# ProPrj_cheap-board_2026-05-07.net
KiCad netlist of a schematic drawn in EasyEDA Pro
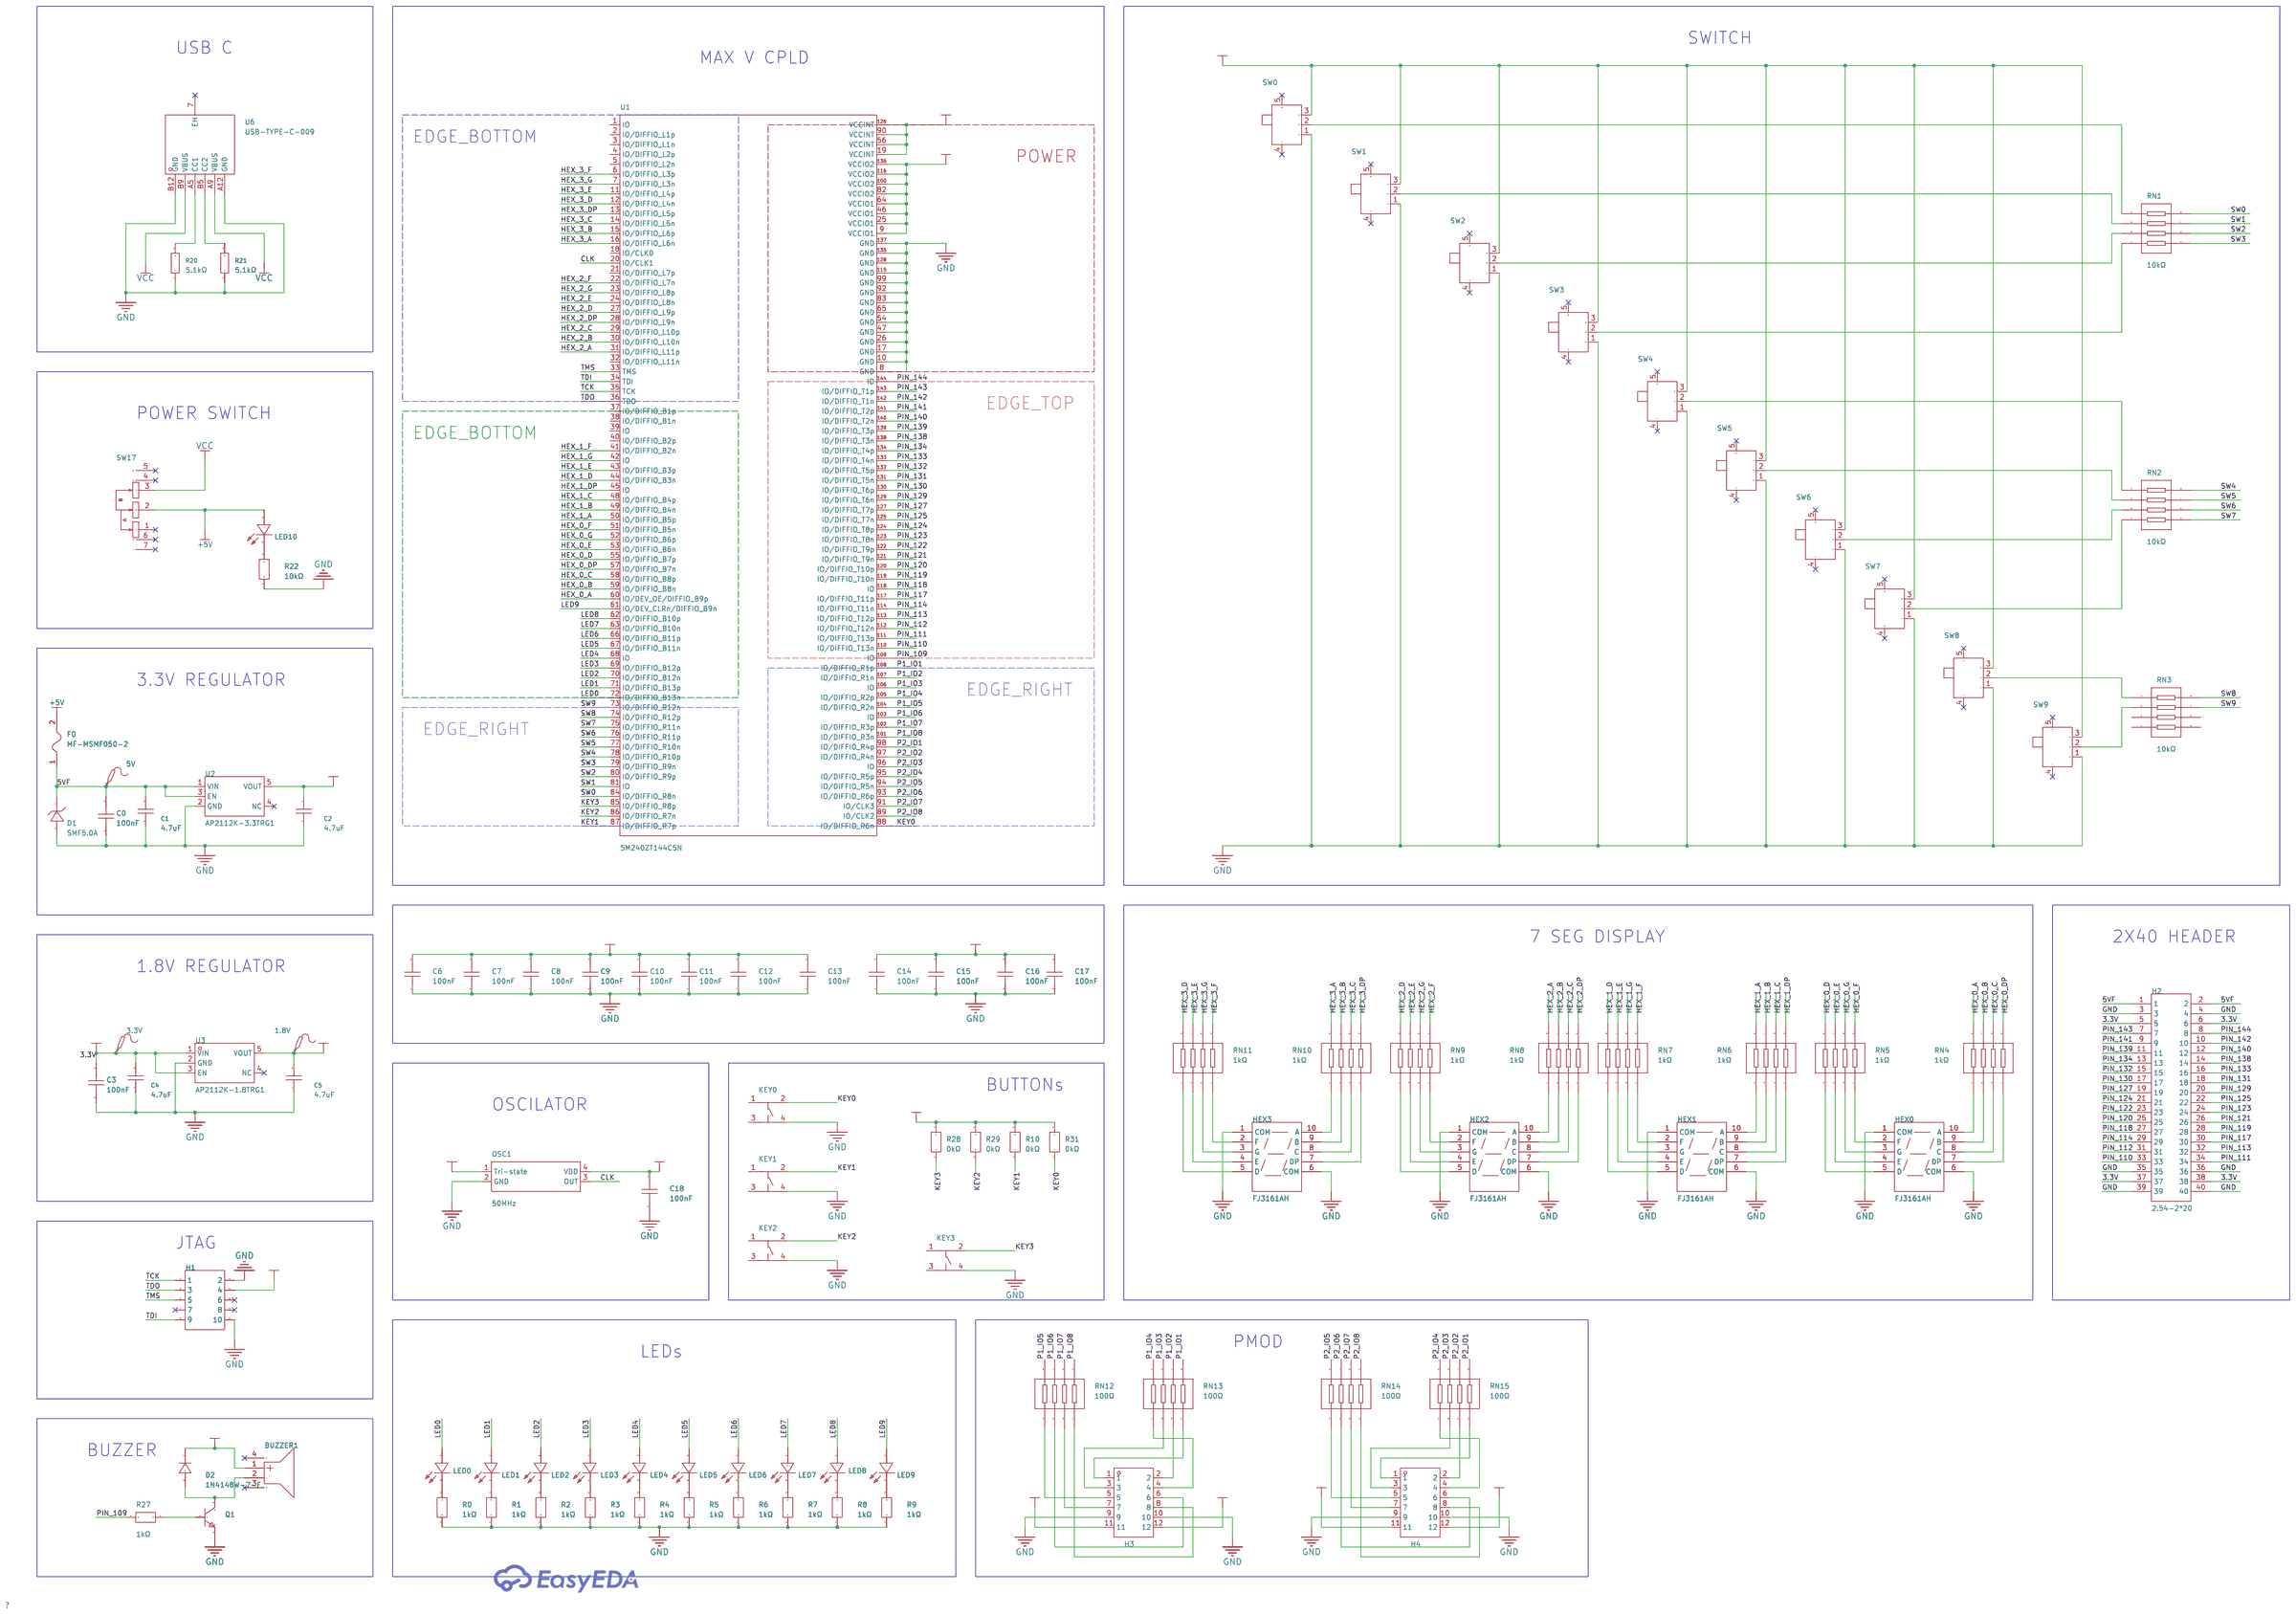
[diagram p0: schematic sheet]

(export (version "E")
  (design (tool "Eeschema 10.0.6"))
  (components
    (comp (ref "1.8V")
      (value "~")
      (footprint "easyedapro:Test-Point-0.5mm")
      (description "Test Point 测试点")
      (libsource (lib "easyedapro") (part "Test-Point"))
    )
    (comp (ref "3.3V")
      (value "~")
      (footprint "easyedapro:Test-Point-0.5mm")
      (description "Test Point 测试点")
      (libsource (lib "easyedapro") (part "Test-Point"))
    )
    (comp (ref "5V")
      (value "~")
      (footprint "easyedapro:Test-Point-0.5mm")
      (description "Test Point 测试点")
      (libsource (lib "easyedapro") (part "Test-Point"))
    )
    (comp (ref "BUZZER1")
      (value "2.7kHz")
      (footprint "easyedapro:BUZ-SMD_4P-L7.5-W7.5-P7.59-TL")
      (fields (field (name "Manufacturer Part") "MLT-7525") (field (name "Manufacturer") "华能"))
      (libsource (lib "easyedapro") (part "MLT-7525"))
    )
    (comp (ref "C0")
      (value "100nF")
      (footprint "easyedapro:C0603")
      (description "Capacitance:100nF Tolerance:±10% Tolerance:±10% Voltage Rating:50V Temperature Coefficient:X7R")
      (fields
        (field (name "Manufacturer Part") "CC0603KRX7R9BB104")
        (field (name "Manufacturer") "YAGEO(国巨)")
      )
      (libsource (lib "easyedapro") (part "CC0603KRX7R9BB104"))
    )
    (comp (ref "C1")
      (value "4.7uF")
      (footprint "easyedapro:C0603")
      (description "Capacitance:4.7uF Tolerance:±10% Tolerance:±10% Voltage Rating:16V Temperature Coefficient:X7R")
      (fields
        (field (name "Manufacturer Part") "CGA0603X7R475K160JT")
        (field (name "Manufacturer") "HRE(芯声)")
      )
      (libsource (lib "easyedapro") (part "CL10A475KP8NNNC"))
    )
    (comp (ref "C2")
      (value "4.7uF")
      (footprint "easyedapro:C0603")
      (description "Capacitance:4.7uF Tolerance:±10% Tolerance:±10% Voltage Rating:16V Temperature Coefficient:X7R")
      (fields
        (field (name "Manufacturer Part") "CGA0603X7R475K160JT")
        (field (name "Manufacturer") "HRE(芯声)")
      )
      (libsource (lib "easyedapro") (part "CL10A475KP8NNNC"))
    )
    (comp (ref "C3")
      (value "100nF")
      (footprint "easyedapro:C0603")
      (description "Capacitance:100nF Tolerance:±10% Tolerance:±10% Voltage Rating:50V Temperature Coefficient:X7R")
      (fields
        (field (name "Manufacturer Part") "CC0603KRX7R9BB104")
        (field (name "Manufacturer") "YAGEO(国巨)")
      )
      (libsource (lib "easyedapro") (part "CC0603KRX7R9BB104"))
    )
    (comp (ref "C4")
      (value "4.7uF")
      (footprint "easyedapro:C0603")
      (description "Capacitance:4.7uF Tolerance:±10% Tolerance:±10% Voltage Rating:16V Temperature Coefficient:X7R")
      (fields
        (field (name "Manufacturer Part") "CGA0603X7R475K160JT")
        (field (name "Manufacturer") "HRE(芯声)")
      )
      (libsource (lib "easyedapro") (part "CL10A475KP8NNNC"))
    )
    (comp (ref "C5")
      (value "4.7uF")
      (footprint "easyedapro:C0603")
      (description "Capacitance:4.7uF Tolerance:±10% Tolerance:±10% Voltage Rating:16V Temperature Coefficient:X7R")
      (fields
        (field (name "Manufacturer Part") "CGA0603X7R475K160JT")
        (field (name "Manufacturer") "HRE(芯声)")
      )
      (libsource (lib "easyedapro") (part "CL10A475KP8NNNC"))
    )
    (comp (ref "C6")
      (value "100nF")
      (footprint "easyedapro:C0603")
      (description "Capacitance:100nF Tolerance:±10% Tolerance:±10% Voltage Rating:50V Temperature Coefficient:X7R")
      (fields
        (field (name "Manufacturer Part") "CC0603KRX7R9BB104")
        (field (name "Manufacturer") "YAGEO(国巨)")
      )
      (libsource (lib "easyedapro") (part "CC0603KRX7R9BB104"))
    )
    (comp (ref "C7")
      (value "100nF")
      (footprint "easyedapro:C0603")
      (description "Capacitance:100nF Tolerance:±10% Tolerance:±10% Voltage Rating:50V Temperature Coefficient:X7R")
      (fields
        (field (name "Manufacturer Part") "CC0603KRX7R9BB104")
        (field (name "Manufacturer") "YAGEO(国巨)")
      )
      (libsource (lib "easyedapro") (part "CC0603KRX7R9BB104"))
    )
    (comp (ref "C8")
      (value "100nF")
      (footprint "easyedapro:C0603")
      (description "Capacitance:100nF Tolerance:±10% Tolerance:±10% Voltage Rating:50V Temperature Coefficient:X7R")
      (fields
        (field (name "Manufacturer Part") "CC0603KRX7R9BB104")
        (field (name "Manufacturer") "YAGEO(国巨)")
      )
      (libsource (lib "easyedapro") (part "CC0603KRX7R9BB104"))
    )
    (comp (ref "C9")
      (value "100nF")
      (footprint "easyedapro:C0603")
      (description "Capacitance:100nF Tolerance:±10% Tolerance:±10% Voltage Rating:50V Temperature Coefficient:X7R")
      (fields
        (field (name "Manufacturer Part") "CC0603KRX7R9BB104")
        (field (name "Manufacturer") "YAGEO(国巨)")
      )
      (libsource (lib "easyedapro") (part "CC0603KRX7R9BB104"))
    )
    (comp (ref "C10")
      (value "100nF")
      (footprint "easyedapro:C0603")
      (description "Capacitance:100nF Tolerance:±10% Tolerance:±10% Voltage Rating:50V Temperature Coefficient:X7R")
      (fields
        (field (name "Manufacturer Part") "CC0603KRX7R9BB104")
        (field (name "Manufacturer") "YAGEO(国巨)")
      )
      (libsource (lib "easyedapro") (part "CC0603KRX7R9BB104"))
    )
    (comp (ref "C11")
      (value "100nF")
      (footprint "easyedapro:C0603")
      (description "Capacitance:100nF Tolerance:±10% Tolerance:±10% Voltage Rating:50V Temperature Coefficient:X7R")
      (fields
        (field (name "Manufacturer Part") "CC0603KRX7R9BB104")
        (field (name "Manufacturer") "YAGEO(国巨)")
      )
      (libsource (lib "easyedapro") (part "CC0603KRX7R9BB104"))
    )
    (comp (ref "C12")
      (value "100nF")
      (footprint "easyedapro:C0603")
      (description "Capacitance:100nF Tolerance:±10% Tolerance:±10% Voltage Rating:50V Temperature Coefficient:X7R")
      (fields
        (field (name "Manufacturer Part") "CC0603KRX7R9BB104")
        (field (name "Manufacturer") "YAGEO(国巨)")
      )
      (libsource (lib "easyedapro") (part "CC0603KRX7R9BB104"))
    )
    (comp (ref "C13")
      (value "100nF")
      (footprint "easyedapro:C0603")
      (description "Capacitance:100nF Tolerance:±10% Tolerance:±10% Voltage Rating:50V Temperature Coefficient:X7R")
      (fields
        (field (name "Manufacturer Part") "CC0603KRX7R9BB104")
        (field (name "Manufacturer") "YAGEO(国巨)")
      )
      (libsource (lib "easyedapro") (part "CC0603KRX7R9BB104"))
    )
    (comp (ref "C14")
      (value "100nF")
      (footprint "easyedapro:C0603")
      (description "Capacitance:100nF Tolerance:±10% Tolerance:±10% Voltage Rating:50V Temperature Coefficient:X7R")
      (fields
        (field (name "Manufacturer Part") "CC0603KRX7R9BB104")
        (field (name "Manufacturer") "YAGEO(国巨)")
      )
      (libsource (lib "easyedapro") (part "CC0603KRX7R9BB104"))
    )
    (comp (ref "C15")
      (value "100nF")
      (footprint "easyedapro:C0603")
      (description "Capacitance:100nF Tolerance:±10% Tolerance:±10% Voltage Rating:50V Temperature Coefficient:X7R")
      (fields
        (field (name "Manufacturer Part") "CC0603KRX7R9BB104")
        (field (name "Manufacturer") "YAGEO(国巨)")
      )
      (libsource (lib "easyedapro") (part "CC0603KRX7R9BB104"))
    )
    (comp (ref "C16")
      (value "100nF")
      (footprint "easyedapro:C0603")
      (description "Capacitance:100nF Tolerance:±10% Tolerance:±10% Voltage Rating:50V Temperature Coefficient:X7R")
      (fields
        (field (name "Manufacturer Part") "CC0603KRX7R9BB104")
        (field (name "Manufacturer") "YAGEO(国巨)")
      )
      (libsource (lib "easyedapro") (part "CC0603KRX7R9BB104"))
    )
    (comp (ref "C17")
      (value "100nF")
      (footprint "easyedapro:C0603")
      (description "Capacitance:100nF Tolerance:±10% Tolerance:±10% Voltage Rating:50V Temperature Coefficient:X7R")
      (fields
        (field (name "Manufacturer Part") "CC0603KRX7R9BB104")
        (field (name "Manufacturer") "YAGEO(国巨)")
      )
      (libsource (lib "easyedapro") (part "CC0603KRX7R9BB104"))
    )
    (comp (ref "C18")
      (value "100nF")
      (footprint "easyedapro:C0603")
      (description "Capacitance:100nF Tolerance:±10% Tolerance:±10% Voltage Rating:50V Temperature Coefficient:X7R")
      (fields
        (field (name "Manufacturer Part") "CC0603KRX7R9BB104")
        (field (name "Manufacturer") "YAGEO(国巨)")
      )
      (libsource (lib "easyedapro") (part "CC0603KRX7R9BB104"))
    )
    (comp (ref "D1")
      (value "SMF5.0A")
      (footprint "easyedapro:SOD-123FL_L2.7-W1.8-LS3.8-RD")
      (fields (field (name "Manufacturer") "MDD(辰达半导体)"))
      (libsource (lib "easyedapro") (part "SMF5.0A_C193402"))
    )
    (comp (ref "D2")
      (value "1N4148W-7-F")
      (footprint "easyedapro:SOD-123_L2.7-W1.6-LS3.7-RD-1")
      (fields (field (name "Manufacturer") "DIODES(美台)"))
      (libsource (lib "easyedapro") (part "1N4148W-7-F"))
    )
    (comp (ref "F0")
      (value "MF-MSMF050-2")
      (footprint "easyedapro:F1812")
      (fields (field (name "Manufacturer") "BOURNS"))
      (libsource (lib "easyedapro") (part "MF-MSMF050-2"))
    )
    (comp (ref "H1")
      (value "2.54-2*5P简牛")
      (footprint "easyedapro:IDC-TH_10P-P2.54_C5665")
      (fields (field (name "Manufacturer") "BOOMELE(博穆精密)"))
      (libsource (lib "easyedapro") (part "HDR-IDC-2.54-2X5P"))
    )
    (comp (ref "H2")
      (value "2.54-2*20")
      (footprint "easyedapro:HDR-TH_40P-P2.54-V-F-R2-C20-S2.54")
      (fields (field (name "Manufacturer") "ZHOURI(洲日)"))
      (libsource (lib "easyedapro") (part "2.54-2*20"))
    )
    (comp (ref "H3")
      (value "HX PM2.54-2x6P WC")
      (footprint "easyedapro:HDR-TH_12P-P2.54-H-F-R2-C6-S2.54-W12.7-N")
      (fields (field (name "Manufacturer") "hanxia(韩下)"))
      (libsource (lib "easyedapro") (part "HX PM2.54-2X6P WC"))
    )
    (comp (ref "H4")
      (value "HX PM2.54-2x6P WC")
      (footprint "easyedapro:HDR-TH_12P-P2.54-H-F-R2-C6-S2.54-W12.7-N")
      (fields (field (name "Manufacturer") "hanxia(韩下)"))
      (libsource (lib "easyedapro") (part "HX PM2.54-2X6P WC"))
    )
    (comp (ref "HEX0")
      (value "FJ3161AH")
      (footprint "easyedapro:LED-SEG-TH_10P-L14.0-W7.5-P2.54-S5.08-TL")
      (description "Digit/Alpha Size(inch):0.36 Illumination Color:Red LED Polarity:Common Cathode")
      (fields (field (name "Manufacturer") "志浩"))
      (libsource (lib "easyedapro") (part "XL-DB3161SRBC"))
    )
    (comp (ref "HEX1")
      (value "FJ3161AH")
      (footprint "easyedapro:LED-SEG-TH_10P-L14.0-W7.5-P2.54-S5.08-TL")
      (description "Digit/Alpha Size(inch):0.36 Illumination Color:Red LED Polarity:Common Cathode")
      (fields (field (name "Manufacturer") "志浩"))
      (libsource (lib "easyedapro") (part "XL-DB3161SRBC"))
    )
    (comp (ref "HEX2")
      (value "FJ3161AH")
      (footprint "easyedapro:LED-SEG-TH_10P-L14.0-W7.5-P2.54-S5.08-TL")
      (description "Digit/Alpha Size(inch):0.36 Illumination Color:Red LED Polarity:Common Cathode")
      (fields (field (name "Manufacturer") "志浩"))
      (libsource (lib "easyedapro") (part "XL-DB3161SRBC"))
    )
    (comp (ref "HEX3")
      (value "FJ3161AH")
      (footprint "easyedapro:LED-SEG-TH_10P-L14.0-W7.5-P2.54-S5.08-TL")
      (description "Digit/Alpha Size(inch):0.36 Illumination Color:Red LED Polarity:Common Cathode")
      (fields (field (name "Manufacturer") "志浩"))
      (libsource (lib "easyedapro") (part "XL-DB3161SRBC"))
    )
    (comp (ref "KEY0")
      (value "KH-6X6X6H-STM")
      (footprint "easyedapro:SW-SMD_4P-L6.0-W6.0-P4.50-LS9.0_KH-6X6X6H-STM")
      (fields (field (name "Manufacturer") "kinghelm(金航标)"))
      (libsource (lib "easyedapro") (part "KH-6X6X6H-STM"))
    )
    (comp (ref "KEY1")
      (value "KH-6X6X6H-STM")
      (footprint "easyedapro:SW-SMD_4P-L6.0-W6.0-P4.50-LS9.0_KH-6X6X6H-STM")
      (fields (field (name "Manufacturer") "kinghelm(金航标)"))
      (libsource (lib "easyedapro") (part "KH-6X6X6H-STM"))
    )
    (comp (ref "KEY2")
      (value "KH-6X6X6H-STM")
      (footprint "easyedapro:SW-SMD_4P-L6.0-W6.0-P4.50-LS9.0_KH-6X6X6H-STM")
      (fields (field (name "Manufacturer") "kinghelm(金航标)"))
      (libsource (lib "easyedapro") (part "KH-6X6X6H-STM"))
    )
    (comp (ref "KEY3")
      (value "KH-6X6X6H-STM")
      (footprint "easyedapro:SW-SMD_4P-L6.0-W6.0-P4.50-LS9.0_KH-6X6X6H-STM")
      (fields (field (name "Manufacturer") "kinghelm(金航标)"))
      (libsource (lib "easyedapro") (part "KH-6X6X6H-STM"))
    )
    (comp (ref "LED0")
      (value "YLED0603R")
      (footprint "easyedapro:LED0805-R-RD")
      (fields (field (name "Manufacturer") "YONGYUTAI(永裕泰)"))
      (libsource (lib "easyedapro") (part "FC-2012HRK-620D"))
    )
    (comp (ref "LED1")
      (value "YLED0603R")
      (footprint "easyedapro:LED0805-R-RD")
      (fields (field (name "Manufacturer") "YONGYUTAI(永裕泰)"))
      (libsource (lib "easyedapro") (part "FC-2012HRK-620D"))
    )
    (comp (ref "LED2")
      (value "YLED0603R")
      (footprint "easyedapro:LED0805-R-RD")
      (fields (field (name "Manufacturer") "YONGYUTAI(永裕泰)"))
      (libsource (lib "easyedapro") (part "FC-2012HRK-620D"))
    )
    (comp (ref "LED3")
      (value "YLED0603R")
      (footprint "easyedapro:LED0805-R-RD")
      (fields (field (name "Manufacturer") "YONGYUTAI(永裕泰)"))
      (libsource (lib "easyedapro") (part "FC-2012HRK-620D"))
    )
    (comp (ref "LED4")
      (value "YLED0603R")
      (footprint "easyedapro:LED0805-R-RD")
      (fields (field (name "Manufacturer") "YONGYUTAI(永裕泰)"))
      (libsource (lib "easyedapro") (part "FC-2012HRK-620D"))
    )
    (comp (ref "LED5")
      (value "YLED0603R")
      (footprint "easyedapro:LED0805-R-RD")
      (fields (field (name "Manufacturer") "YONGYUTAI(永裕泰)"))
      (libsource (lib "easyedapro") (part "FC-2012HRK-620D"))
    )
    (comp (ref "LED6")
      (value "YLED0603R")
      (footprint "easyedapro:LED0805-R-RD")
      (fields (field (name "Manufacturer") "YONGYUTAI(永裕泰)"))
      (libsource (lib "easyedapro") (part "FC-2012HRK-620D"))
    )
    (comp (ref "LED7")
      (value "YLED0603R")
      (footprint "easyedapro:LED0805-R-RD")
      (fields (field (name "Manufacturer") "YONGYUTAI(永裕泰)"))
      (libsource (lib "easyedapro") (part "FC-2012HRK-620D"))
    )
    (comp (ref "LED8")
      (value "YLED0603R")
      (footprint "easyedapro:LED0805-R-RD")
      (fields (field (name "Manufacturer") "YONGYUTAI(永裕泰)"))
      (libsource (lib "easyedapro") (part "FC-2012HRK-620D"))
    )
    (comp (ref "LED9")
      (value "YLED0603R")
      (footprint "easyedapro:LED0805-R-RD")
      (fields (field (name "Manufacturer") "YONGYUTAI(永裕泰)"))
      (libsource (lib "easyedapro") (part "FC-2012HRK-620D"))
    )
    (comp (ref "LED10")
      (value "YLED0603R")
      (footprint "easyedapro:LED0805-R-RD")
      (fields (field (name "Manufacturer") "YONGYUTAI(永裕泰)"))
      (libsource (lib "easyedapro") (part "FC-2012HRK-620D"))
    )
    (comp (ref "OSC1")
      (value "50MHz")
      (footprint "easyedapro:OSC-SMD_4P-L3.2-W2.5-BL")
      (fields
        (field (name "Manufacturer Part") "OT2EL4C4JI-111OLP-50M")
        (field (name "Manufacturer") "YXC(扬兴晶振)")
      )
      (libsource (lib "easyedapro") (part "OT2EL4C4JI-111OLP-50M"))
    )
    (comp (ref "Q1")
      (value "MMBT3904LT1G")
      (footprint "easyedapro:SOT-23-3_L2.9-W1.6-P1.90-LS2.8-BR")
      (fields (field (name "Manufacturer") "onsemi(安森美)"))
      (libsource (lib "easyedapro") (part "MMBT3904LT1G"))
    )
    (comp (ref "R0")
      (value "1kΩ")
      (fields (field (name "Manufacturer Part") "RC0603FR-071KL") (field (name "Manufacturer") "YAGEO(国巨)"))
      (libsource (lib "easyedapro") (part "SC1206J1500F8ANRH"))
    )
    (comp (ref "R1")
      (value "1kΩ")
      (fields (field (name "Manufacturer Part") "RC0603FR-071KL") (field (name "Manufacturer") "YAGEO(国巨)"))
      (libsource (lib "easyedapro") (part "SC1206J1500F8ANRH"))
    )
    (comp (ref "R2")
      (value "1kΩ")
      (fields (field (name "Manufacturer Part") "RC0603FR-071KL") (field (name "Manufacturer") "YAGEO(国巨)"))
      (libsource (lib "easyedapro") (part "SC1206J1500F8ANRH"))
    )
    (comp (ref "R3")
      (value "1kΩ")
      (fields (field (name "Manufacturer Part") "RC0603FR-071KL") (field (name "Manufacturer") "YAGEO(国巨)"))
      (libsource (lib "easyedapro") (part "SC1206J1500F8ANRH"))
    )
    (comp (ref "R4")
      (value "1kΩ")
      (fields (field (name "Manufacturer Part") "RC0603FR-071KL") (field (name "Manufacturer") "YAGEO(国巨)"))
      (libsource (lib "easyedapro") (part "SC1206J1500F8ANRH"))
    )
    (comp (ref "R5")
      (value "1kΩ")
      (fields (field (name "Manufacturer Part") "RC0603FR-071KL") (field (name "Manufacturer") "YAGEO(国巨)"))
      (libsource (lib "easyedapro") (part "SC1206J1500F8ANRH"))
    )
    (comp (ref "R6")
      (value "1kΩ")
      (fields (field (name "Manufacturer Part") "RC0603FR-071KL") (field (name "Manufacturer") "YAGEO(国巨)"))
      (libsource (lib "easyedapro") (part "SC1206J1500F8ANRH"))
    )
    (comp (ref "R7")
      (value "1kΩ")
      (fields (field (name "Manufacturer Part") "RC0603FR-071KL") (field (name "Manufacturer") "YAGEO(国巨)"))
      (libsource (lib "easyedapro") (part "SC1206J1500F8ANRH"))
    )
    (comp (ref "R8")
      (value "1kΩ")
      (fields (field (name "Manufacturer Part") "RC0603FR-071KL") (field (name "Manufacturer") "YAGEO(国巨)"))
      (libsource (lib "easyedapro") (part "SC1206J1500F8ANRH"))
    )
    (comp (ref "R9")
      (value "1kΩ")
      (fields (field (name "Manufacturer Part") "RC0603FR-071KL") (field (name "Manufacturer") "YAGEO(国巨)"))
      (libsource (lib "easyedapro") (part "SC1206J1500F8ANRH"))
    )
    (comp (ref "R10")
      (value "0kΩ")
      (fields (field (name "Manufacturer Part") "RC0603FR-071KL") (field (name "Manufacturer") "YAGEO(国巨)"))
      (libsource (lib "easyedapro") (part "SC1206J1500F8ANRH"))
    )
    (comp (ref "R20")
      (value "5.1kΩ")
      (footprint "easyedapro:R0603")
      (fields (field (name "Manufacturer Part") "RMC06035.1K1%N") (field (name "Manufacturer") "Tyohm(幸亚电阻)"))
      (libsource (lib "easyedapro") (part "RMC06035.1K1%N"))
    )
    (comp (ref "R21")
      (value "5.1kΩ")
      (footprint "easyedapro:R0603")
      (fields (field (name "Manufacturer Part") "RMC06035.1K1%N") (field (name "Manufacturer") "Tyohm(幸亚电阻)"))
      (libsource (lib "easyedapro") (part "RMC06035.1K1%N"))
    )
    (comp (ref "R22")
      (value "10kΩ")
      (fields (field (name "Manufacturer Part") "RC0603FR-071KL") (field (name "Manufacturer") "YAGEO(国巨)"))
      (libsource (lib "easyedapro") (part "SC1206J1500F8ANRH"))
    )
    (comp (ref "R27")
      (value "1kΩ")
      (fields (field (name "Manufacturer Part") "RC0603FR-071KL") (field (name "Manufacturer") "YAGEO(国巨)"))
      (libsource (lib "easyedapro") (part "SC1206J1500F8ANRH"))
    )
    (comp (ref "R28")
      (value "0kΩ")
      (fields (field (name "Manufacturer Part") "RC0603FR-071KL") (field (name "Manufacturer") "YAGEO(国巨)"))
      (libsource (lib "easyedapro") (part "SC1206J1500F8ANRH"))
    )
    (comp (ref "R29")
      (value "0kΩ")
      (fields (field (name "Manufacturer Part") "RC0603FR-071KL") (field (name "Manufacturer") "YAGEO(国巨)"))
      (libsource (lib "easyedapro") (part "SC1206J1500F8ANRH"))
    )
    (comp (ref "R31")
      (value "0kΩ")
      (fields (field (name "Manufacturer Part") "RC0603FR-071KL") (field (name "Manufacturer") "YAGEO(国巨)"))
      (libsource (lib "easyedapro") (part "SC1206J1500F8ANRH"))
    )
    (comp (ref "RN1")
      (value "10kΩ")
      (footprint "easyedapro:RES-ARRAY-SMD_0603-8P-L3.2-W1.6-BL")
      (fields
        (field (name "Manufacturer Part") "4D03WGJ0103T5E")
        (field (name "Manufacturer") "UNI-ROYAL(厚声)")
      )
      (libsource (lib "easyedapro") (part "4D03WGJ0103T5E"))
    )
    (comp (ref "RN2")
      (value "10kΩ")
      (footprint "easyedapro:RES-ARRAY-SMD_0603-8P-L3.2-W1.6-BL")
      (fields
        (field (name "Manufacturer Part") "4D03WGJ0103T5E")
        (field (name "Manufacturer") "UNI-ROYAL(厚声)")
      )
      (libsource (lib "easyedapro") (part "4D03WGJ0103T5E"))
    )
    (comp (ref "RN3")
      (value "10kΩ")
      (footprint "easyedapro:RES-ARRAY-SMD_0603-8P-L3.2-W1.6-BL")
      (fields
        (field (name "Manufacturer Part") "4D03WGJ0103T5E")
        (field (name "Manufacturer") "UNI-ROYAL(厚声)")
      )
      (libsource (lib "easyedapro") (part "4D03WGJ0103T5E"))
    )
    (comp (ref "RN4")
      (value "1kΩ")
      (footprint "easyedapro:RES-ARRAY-SMD_0603-8P-L3.2-W1.6-BL")
      (fields
        (field (name "Manufacturer Part") "4D03WGJ0102T5E")
        (field (name "Manufacturer") "UNI-ROYAL(厚声)")
      )
      (libsource (lib "easyedapro") (part "4D03WGJ0102T5E"))
    )
    (comp (ref "RN5")
      (value "1kΩ")
      (footprint "easyedapro:RES-ARRAY-SMD_0603-8P-L3.2-W1.6-BL")
      (fields
        (field (name "Manufacturer Part") "4D03WGJ0102T5E")
        (field (name "Manufacturer") "UNI-ROYAL(厚声)")
      )
      (libsource (lib "easyedapro") (part "4D03WGJ0102T5E"))
    )
    (comp (ref "RN6")
      (value "1kΩ")
      (footprint "easyedapro:RES-ARRAY-SMD_0603-8P-L3.2-W1.6-BL")
      (fields
        (field (name "Manufacturer Part") "4D03WGJ0102T5E")
        (field (name "Manufacturer") "UNI-ROYAL(厚声)")
      )
      (libsource (lib "easyedapro") (part "4D03WGJ0102T5E"))
    )
    (comp (ref "RN7")
      (value "1kΩ")
      (footprint "easyedapro:RES-ARRAY-SMD_0603-8P-L3.2-W1.6-BL")
      (fields
        (field (name "Manufacturer Part") "4D03WGJ0102T5E")
        (field (name "Manufacturer") "UNI-ROYAL(厚声)")
      )
      (libsource (lib "easyedapro") (part "4D03WGJ0102T5E"))
    )
    (comp (ref "RN8")
      (value "1kΩ")
      (footprint "easyedapro:RES-ARRAY-SMD_0603-8P-L3.2-W1.6-BL")
      (fields
        (field (name "Manufacturer Part") "4D03WGJ0102T5E")
        (field (name "Manufacturer") "UNI-ROYAL(厚声)")
      )
      (libsource (lib "easyedapro") (part "4D03WGJ0102T5E"))
    )
    (comp (ref "RN9")
      (value "1kΩ")
      (footprint "easyedapro:RES-ARRAY-SMD_0603-8P-L3.2-W1.6-BL")
      (fields
        (field (name "Manufacturer Part") "4D03WGJ0102T5E")
        (field (name "Manufacturer") "UNI-ROYAL(厚声)")
      )
      (libsource (lib "easyedapro") (part "4D03WGJ0102T5E"))
    )
    (comp (ref "RN10")
      (value "1kΩ")
      (footprint "easyedapro:RES-ARRAY-SMD_0603-8P-L3.2-W1.6-BL")
      (fields
        (field (name "Manufacturer Part") "4D03WGJ0102T5E")
        (field (name "Manufacturer") "UNI-ROYAL(厚声)")
      )
      (libsource (lib "easyedapro") (part "4D03WGJ0102T5E"))
    )
    (comp (ref "RN11")
      (value "1kΩ")
      (footprint "easyedapro:RES-ARRAY-SMD_0603-8P-L3.2-W1.6-BL")
      (fields
        (field (name "Manufacturer Part") "4D03WGJ0102T5E")
        (field (name "Manufacturer") "UNI-ROYAL(厚声)")
      )
      (libsource (lib "easyedapro") (part "4D03WGJ0102T5E"))
    )
    (comp (ref "RN12")
      (value "100Ω")
      (footprint "easyedapro:RES-ARRAY-SMD_0603-8P-L3.2-W1.6-BL")
      (fields (field (name "Manufacturer Part") "YC164-FR-07100RL") (field (name "Manufacturer") "YAGEO(国巨)"))
      (libsource (lib "easyedapro") (part "YC164-FR-07100RL"))
    )
    (comp (ref "RN13")
      (value "100Ω")
      (footprint "easyedapro:RES-ARRAY-SMD_0603-8P-L3.2-W1.6-BL")
      (fields (field (name "Manufacturer Part") "YC164-FR-07100RL") (field (name "Manufacturer") "YAGEO(国巨)"))
      (libsource (lib "easyedapro") (part "YC164-FR-07100RL"))
    )
    (comp (ref "RN14")
      (value "100Ω")
      (footprint "easyedapro:RES-ARRAY-SMD_0603-8P-L3.2-W1.6-BL")
      (fields (field (name "Manufacturer Part") "YC164-FR-07100RL") (field (name "Manufacturer") "YAGEO(国巨)"))
      (libsource (lib "easyedapro") (part "YC164-FR-07100RL"))
    )
    (comp (ref "RN15")
      (value "100Ω")
      (footprint "easyedapro:RES-ARRAY-SMD_0603-8P-L3.2-W1.6-BL")
      (fields (field (name "Manufacturer Part") "YC164-FR-07100RL") (field (name "Manufacturer") "YAGEO(国巨)"))
      (libsource (lib "easyedapro") (part "YC164-FR-07100RL"))
    )
    (comp (ref "SW0")
      (value "SS12F44G4")
      (fields (field (name "Manufacturer") "SHOU HAN(首韩)"))
      (libsource (lib "easyedapro") (part "SS12D07VG4 087"))
    )
    (comp (ref "SW1")
      (value "SS12F44G4")
      (fields (field (name "Manufacturer") "SHOU HAN(首韩)"))
      (libsource (lib "easyedapro") (part "SS12D07VG4 087"))
    )
    (comp (ref "SW2")
      (value "SS12F44G4")
      (fields (field (name "Manufacturer") "SHOU HAN(首韩)"))
      (libsource (lib "easyedapro") (part "SS12D07VG4 087"))
    )
    (comp (ref "SW3")
      (value "SS12F44G4")
      (fields (field (name "Manufacturer") "SHOU HAN(首韩)"))
      (libsource (lib "easyedapro") (part "SS12D07VG4 087"))
    )
    (comp (ref "SW4")
      (value "SS12F44G4")
      (fields (field (name "Manufacturer") "SHOU HAN(首韩)"))
      (libsource (lib "easyedapro") (part "SS12D07VG4 087"))
    )
    (comp (ref "SW5")
      (value "SS12F44G4")
      (fields (field (name "Manufacturer") "SHOU HAN(首韩)"))
      (libsource (lib "easyedapro") (part "SS12D07VG4 087"))
    )
    (comp (ref "SW6")
      (value "SS12F44G4")
      (fields (field (name "Manufacturer") "SHOU HAN(首韩)"))
      (libsource (lib "easyedapro") (part "SS12D07VG4 087"))
    )
    (comp (ref "SW7")
      (value "SS12F44G4")
      (fields (field (name "Manufacturer") "SHOU HAN(首韩)"))
      (libsource (lib "easyedapro") (part "SS12D07VG4 087"))
    )
    (comp (ref "SW8")
      (value "SS12F44G4")
      (fields (field (name "Manufacturer") "SHOU HAN(首韩)"))
      (libsource (lib "easyedapro") (part "SS12D07VG4 087"))
    )
    (comp (ref "SW9")
      (value "SS12F44G4")
      (fields (field (name "Manufacturer") "SHOU HAN(首韩)"))
      (libsource (lib "easyedapro") (part "SS12D07VG4 087"))
    )
    (comp (ref "SW17")
      (value "MK-12C02-G020")
      (fields (field (name "Manufacturer") "G-Switch(品赞)"))
      (libsource (lib "easyedapro") (part "MK-12C02-G015"))
    )
    (comp (ref "U1")
      (value "5M240ZT144C5N")
      (footprint "easyedapro:TQFP-144_L20.0-W20.0-P0.50-LS22.0-BL")
      (fields (field (name "Manufacturer") "Intel/Altera"))
      (libsource (lib "easyedapro") (part "5M240ZT144C5N"))
    )
    (comp (ref "U2")
      (value "AP2112K-3.3TRG1")
      (footprint "easyedapro:SOT-23-5_L2.9-W1.6-P0.95-LS2.8-BR")
      (fields (field (name "Manufacturer") "TECH PUBLIC(台舟)"))
      (libsource (lib "easyedapro") (part "AP2112K-3.3TRG1_C23380830"))
    )
    (comp (ref "U3")
      (value "AP2112K-1.8TRG1")
      (footprint "easyedapro:SOT-25_L3.0-W1.6-P0.95-LS2.8-BL")
      (fields (field (name "Manufacturer") "DIODES(美台)"))
      (libsource (lib "easyedapro") (part "AP2112K-1.8TRG1"))
    )
    (comp (ref "U6")
      (value "USB-TYPE-C-009")
      (footprint "easyedapro:TYPE-C-SMD_TYPE-C-6P")
      (fields (field (name "Manufacturer") "DEALON(德艺隆)"))
      (libsource (lib "easyedapro") (part "USB-TYPE-C-009"))
    )
  )
  (nets
    (net (code "1") (name "+5V") (class "Default")
      (node (ref "F0") (pin "2") (pinfunction "2_2") (pintype "unspecified"))
      (node (ref "LED10") (pin "1") (pinfunction "+_1") (pintype "unspecified"))
      (node (ref "SW17") (pin "2") (pinfunction "2_2") (pintype "unspecified"))
    )
    (net (code "2") (name "/5VF") (class "Default")
      (node (ref "5V") (pin "1") (pinfunction "1_1") (pintype "unspecified"))
      (node (ref "C0") (pin "2") (pinfunction "2_2") (pintype "unspecified"))
      (node (ref "C1") (pin "2") (pinfunction "2_2") (pintype "input"))
      (node (ref "D1") (pin "1") (pinfunction "C_1") (pintype "unspecified"))
      (node (ref "F0") (pin "1") (pinfunction "1_1") (pintype "unspecified"))
      (node (ref "H2") (pin "1") (pinfunction "1_1") (pintype "unspecified"))
      (node (ref "H2") (pin "2") (pinfunction "2_2") (pintype "unspecified"))
      (node (ref "U2") (pin "1") (pinfunction "VIN_1") (pintype "unspecified"))
      (node (ref "U2") (pin "3") (pinfunction "EN_3") (pintype "unspecified"))
    )
    (net (code "3") (name "/CLK") (class "Default")
      (node (ref "OSC1") (pin "3") (pinfunction "OUT_3") (pintype "unspecified"))
      (node (ref "U1") (pin "20") (pinfunction "IO/CLK1_20") (pintype "unspecified"))
    )
    (net (code "4") (name "/HEX_0_A") (class "Default")
      (node (ref "RN4") (pin "8") (pinfunction "8_8") (pintype "input"))
      (node (ref "U1") (pin "60") (pinfunction "IO/DEV_OE/DIFFIO_B9p_60") (pintype "unspecified"))
    )
    (net (code "5") (name "/HEX_0_B") (class "Default")
      (node (ref "RN4") (pin "7") (pinfunction "7_7") (pintype "input"))
      (node (ref "U1") (pin "59") (pinfunction "IO/DIFFIO_B8n_59") (pintype "unspecified"))
    )
    (net (code "6") (name "/HEX_0_C") (class "Default")
      (node (ref "RN4") (pin "6") (pinfunction "6_6") (pintype "input"))
      (node (ref "U1") (pin "58") (pinfunction "IO/DIFFIO_B8p_58") (pintype "unspecified"))
    )
    (net (code "7") (name "/HEX_0_D") (class "Default")
      (node (ref "RN5") (pin "8") (pinfunction "8_8") (pintype "input"))
      (node (ref "U1") (pin "55") (pinfunction "IO/DIFFIO_B7p_55") (pintype "unspecified"))
    )
    (net (code "8") (name "/HEX_0_DP") (class "Default")
      (node (ref "RN4") (pin "5") (pinfunction "5_5") (pintype "input"))
      (node (ref "U1") (pin "57") (pinfunction "IO/DIFFIO_B7n_57") (pintype "unspecified"))
    )
    (net (code "9") (name "/HEX_0_E") (class "Default")
      (node (ref "RN5") (pin "7") (pinfunction "7_7") (pintype "input"))
      (node (ref "U1") (pin "53") (pinfunction "IO/DIFFIO_B6n_53") (pintype "unspecified"))
    )
    (net (code "10") (name "/HEX_0_F") (class "Default")
      (node (ref "RN5") (pin "5") (pinfunction "5_5") (pintype "input"))
      (node (ref "U1") (pin "51") (pinfunction "IO/DIFFIO_B5n_51") (pintype "unspecified"))
    )
    (net (code "11") (name "/HEX_0_G") (class "Default")
      (node (ref "RN5") (pin "6") (pinfunction "6_6") (pintype "input"))
      (node (ref "U1") (pin "52") (pinfunction "IO/DIFFIO_B6p_52") (pintype "unspecified"))
    )
    (net (code "12") (name "/HEX_1_A") (class "Default")
      (node (ref "RN6") (pin "8") (pinfunction "8_8") (pintype "input"))
      (node (ref "U1") (pin "50") (pinfunction "IO/DIFFIO_B5p_50") (pintype "unspecified"))
    )
    (net (code "13") (name "/HEX_1_B") (class "Default")
      (node (ref "RN6") (pin "7") (pinfunction "7_7") (pintype "input"))
      (node (ref "U1") (pin "49") (pinfunction "IO/DIFFIO_B4n_49") (pintype "unspecified"))
    )
    (net (code "14") (name "/HEX_1_C") (class "Default")
      (node (ref "RN6") (pin "6") (pinfunction "6_6") (pintype "input"))
      (node (ref "U1") (pin "48") (pinfunction "IO/DIFFIO_B4p_48") (pintype "unspecified"))
    )
    (net (code "15") (name "/HEX_1_D") (class "Default")
      (node (ref "RN7") (pin "8") (pinfunction "8_8") (pintype "input"))
      (node (ref "U1") (pin "44") (pinfunction "IO/DIFFIO_B3n_44") (pintype "unspecified"))
    )
    (net (code "16") (name "/HEX_1_DP") (class "Default")
      (node (ref "RN6") (pin "5") (pinfunction "5_5") (pintype "input"))
      (node (ref "U1") (pin "45") (pinfunction "IO_45") (pintype "unspecified"))
    )
    (net (code "17") (name "/HEX_1_E") (class "Default")
      (node (ref "RN7") (pin "7") (pinfunction "7_7") (pintype "input"))
      (node (ref "U1") (pin "43") (pinfunction "IO/DIFFIO_B3p_43") (pintype "unspecified"))
    )
    (net (code "18") (name "/HEX_1_F") (class "Default")
      (node (ref "RN7") (pin "5") (pinfunction "5_5") (pintype "input"))
      (node (ref "U1") (pin "41") (pinfunction "IO/DIFFIO_B2n_41") (pintype "unspecified"))
    )
    (net (code "19") (name "/HEX_1_G") (class "Default")
      (node (ref "RN7") (pin "6") (pinfunction "6_6") (pintype "input"))
      (node (ref "U1") (pin "42") (pinfunction "IO_42") (pintype "unspecified"))
    )
    (net (code "20") (name "/HEX_2_A") (class "Default")
      (node (ref "RN8") (pin "8") (pinfunction "8_8") (pintype "input"))
      (node (ref "U1") (pin "31") (pinfunction "IO/DIFFIO_L11p_31") (pintype "unspecified"))
    )
    (net (code "21") (name "/HEX_2_B") (class "Default")
      (node (ref "RN8") (pin "7") (pinfunction "7_7") (pintype "input"))
      (node (ref "U1") (pin "30") (pinfunction "IO/DIFFIO_L10n_30") (pintype "unspecified"))
    )
    (net (code "22") (name "/HEX_2_C") (class "Default")
      (node (ref "RN8") (pin "6") (pinfunction "6_6") (pintype "input"))
      (node (ref "U1") (pin "29") (pinfunction "IO/DIFFIO_L10p_29") (pintype "unspecified"))
    )
    (net (code "23") (name "/HEX_2_D") (class "Default")
      (node (ref "RN9") (pin "8") (pinfunction "8_8") (pintype "input"))
      (node (ref "U1") (pin "27") (pinfunction "IO/DIFFIO_L9p_27") (pintype "unspecified"))
    )
    (net (code "24") (name "/HEX_2_DP") (class "Default")
      (node (ref "RN8") (pin "5") (pinfunction "5_5") (pintype "input"))
      (node (ref "U1") (pin "28") (pinfunction "IO/DIFFIO_L9n_28") (pintype "unspecified"))
    )
    (net (code "25") (name "/HEX_2_E") (class "Default")
      (node (ref "RN9") (pin "7") (pinfunction "7_7") (pintype "input"))
      (node (ref "U1") (pin "24") (pinfunction "IO/DIFFIO_L8n_24") (pintype "unspecified"))
    )
    (net (code "26") (name "/HEX_2_F") (class "Default")
      (node (ref "RN9") (pin "5") (pinfunction "5_5") (pintype "input"))
      (node (ref "U1") (pin "22") (pinfunction "IO/DIFFIO_L7n_22") (pintype "unspecified"))
    )
    (net (code "27") (name "/HEX_2_G") (class "Default")
      (node (ref "RN9") (pin "6") (pinfunction "6_6") (pintype "input"))
      (node (ref "U1") (pin "23") (pinfunction "IO/DIFFIO_L8p_23") (pintype "unspecified"))
    )
    (net (code "28") (name "/HEX_3_A") (class "Default")
      (node (ref "RN10") (pin "8") (pinfunction "8_8") (pintype "input"))
      (node (ref "U1") (pin "16") (pinfunction "IO/DIFFIO_L6n_16") (pintype "unspecified"))
    )
    (net (code "29") (name "/HEX_3_B") (class "Default")
      (node (ref "RN10") (pin "7") (pinfunction "7_7") (pintype "input"))
      (node (ref "U1") (pin "15") (pinfunction "IO/DIFFIO_L6p_15") (pintype "unspecified"))
    )
    (net (code "30") (name "/HEX_3_C") (class "Default")
      (node (ref "RN10") (pin "6") (pinfunction "6_6") (pintype "input"))
      (node (ref "U1") (pin "14") (pinfunction "IO/DIFFIO_L5n_14") (pintype "unspecified"))
    )
    (net (code "31") (name "/HEX_3_D") (class "Default")
      (node (ref "RN11") (pin "8") (pinfunction "8_8") (pintype "input"))
      (node (ref "U1") (pin "12") (pinfunction "IO/DIFFIO_L4n_12") (pintype "unspecified"))
    )
    (net (code "32") (name "/HEX_3_DP") (class "Default")
      (node (ref "RN10") (pin "5") (pinfunction "5_5") (pintype "input"))
      (node (ref "U1") (pin "13") (pinfunction "IO/DIFFIO_L5p_13") (pintype "unspecified"))
    )
    (net (code "33") (name "/HEX_3_E") (class "Default")
      (node (ref "RN11") (pin "7") (pinfunction "7_7") (pintype "input"))
      (node (ref "U1") (pin "11") (pinfunction "IO/DIFFIO_L4p_11") (pintype "unspecified"))
    )
    (net (code "34") (name "/HEX_3_F") (class "Default")
      (node (ref "RN11") (pin "5") (pinfunction "5_5") (pintype "input"))
      (node (ref "U1") (pin "6") (pinfunction "IO/DIFFIO_L3p_6") (pintype "unspecified"))
    )
    (net (code "35") (name "/HEX_3_G") (class "Default")
      (node (ref "RN11") (pin "6") (pinfunction "6_6") (pintype "input"))
      (node (ref "U1") (pin "7") (pinfunction "IO/DIFFIO_L3n_7") (pintype "unspecified"))
    )
    (net (code "36") (name "/KEY0") (class "Default")
      (node (ref "KEY0") (pin "2") (pinfunction "B_2") (pintype "unspecified"))
      (node (ref "R31") (pin "1") (pinfunction "1_1") (pintype "unspecified"))
      (node (ref "U1") (pin "88") (pinfunction "IO/DIFFIO_R6n_88") (pintype "unspecified"))
    )
    (net (code "37") (name "/KEY1") (class "Default")
      (node (ref "KEY1") (pin "2") (pinfunction "B_2") (pintype "unspecified"))
      (node (ref "R10") (pin "1") (pinfunction "1_1") (pintype "unspecified"))
      (node (ref "U1") (pin "87") (pinfunction "IO/DIFFIO_R7p_87") (pintype "unspecified"))
    )
    (net (code "38") (name "/KEY2") (class "Default")
      (node (ref "KEY2") (pin "2") (pinfunction "B_2") (pintype "unspecified"))
      (node (ref "R29") (pin "1") (pinfunction "1_1") (pintype "unspecified"))
      (node (ref "U1") (pin "86") (pinfunction "IO/DIFFIO_R7n_86") (pintype "unspecified"))
    )
    (net (code "39") (name "/KEY3") (class "Default")
      (node (ref "KEY3") (pin "2") (pinfunction "B_2") (pintype "unspecified"))
      (node (ref "R28") (pin "1") (pinfunction "1_1") (pintype "unspecified"))
      (node (ref "U1") (pin "85") (pinfunction "IO/DIFFIO_R8p_85") (pintype "unspecified"))
    )
    (net (code "40") (name "/LED0") (class "Default")
      (node (ref "LED0") (pin "1") (pinfunction "+_1") (pintype "unspecified"))
      (node (ref "U1") (pin "72") (pinfunction "IO/DIFFIO_B13n_72") (pintype "unspecified"))
    )
    (net (code "41") (name "/LED1") (class "Default")
      (node (ref "LED1") (pin "1") (pinfunction "+_1") (pintype "unspecified"))
      (node (ref "U1") (pin "71") (pinfunction "IO/DIFFIO_B13p_71") (pintype "unspecified"))
    )
    (net (code "42") (name "/LED2") (class "Default")
      (node (ref "LED2") (pin "1") (pinfunction "+_1") (pintype "unspecified"))
      (node (ref "U1") (pin "70") (pinfunction "IO/DIFFIO_B12n_70") (pintype "unspecified"))
    )
    (net (code "43") (name "/LED3") (class "Default")
      (node (ref "LED3") (pin "1") (pinfunction "+_1") (pintype "unspecified"))
      (node (ref "U1") (pin "69") (pinfunction "IO/DIFFIO_B12p_69") (pintype "unspecified"))
    )
    (net (code "44") (name "/LED4") (class "Default")
      (node (ref "LED4") (pin "1") (pinfunction "+_1") (pintype "unspecified"))
      (node (ref "U1") (pin "68") (pinfunction "IO_68") (pintype "unspecified"))
    )
    (net (code "45") (name "/LED5") (class "Default")
      (node (ref "LED5") (pin "1") (pinfunction "+_1") (pintype "unspecified"))
      (node (ref "U1") (pin "67") (pinfunction "IO/DIFFIO_B11n_67") (pintype "unspecified"))
    )
    (net (code "46") (name "/LED6") (class "Default")
      (node (ref "LED6") (pin "1") (pinfunction "+_1") (pintype "unspecified"))
      (node (ref "U1") (pin "66") (pinfunction "IO/DIFFIO_B11p_66") (pintype "unspecified"))
    )
    (net (code "47") (name "/LED7") (class "Default")
      (node (ref "LED7") (pin "1") (pinfunction "+_1") (pintype "unspecified"))
      (node (ref "U1") (pin "63") (pinfunction "IO/DIFFIO_B10n_63") (pintype "unspecified"))
    )
    (net (code "48") (name "/LED8") (class "Default")
      (node (ref "LED8") (pin "1") (pinfunction "+_1") (pintype "unspecified"))
      (node (ref "U1") (pin "62") (pinfunction "IO/DIFFIO_B10p_62") (pintype "unspecified"))
    )
    (net (code "49") (name "/LED9") (class "Default")
      (node (ref "LED9") (pin "1") (pinfunction "+_1") (pintype "unspecified"))
      (node (ref "U1") (pin "61") (pinfunction "IO/DEV_CLRn/DIFFIO_B9n_61") (pintype "unspecified"))
    )
    (net (code "50") (name "/P1_IO1") (class "Default")
      (node (ref "RN13") (pin "8") (pinfunction "8_8") (pintype "input"))
      (node (ref "U1") (pin "108") (pinfunction "IO/DIFFIO_R1p_108") (pintype "unspecified"))
    )
    (net (code "51") (name "/P1_IO2") (class "Default")
      (node (ref "RN13") (pin "7") (pinfunction "7_7") (pintype "input"))
      (node (ref "U1") (pin "107") (pinfunction "IO/DIFFIO_R1n_107") (pintype "unspecified"))
    )
    (net (code "52") (name "/P1_IO3") (class "Default")
      (node (ref "RN13") (pin "6") (pinfunction "6_6") (pintype "input"))
      (node (ref "U1") (pin "106") (pinfunction "IO_106") (pintype "unspecified"))
    )
    (net (code "53") (name "/P1_IO4") (class "Default")
      (node (ref "RN13") (pin "5") (pinfunction "5_5") (pintype "input"))
      (node (ref "U1") (pin "105") (pinfunction "IO/DIFFIO_R2p_105") (pintype "unspecified"))
    )
    (net (code "54") (name "/P1_IO5") (class "Default")
      (node (ref "RN12") (pin "8") (pinfunction "8_8") (pintype "input"))
      (node (ref "U1") (pin "104") (pinfunction "IO/DIFFIO_R2n_104") (pintype "unspecified"))
    )
    (net (code "55") (name "/P1_IO6") (class "Default")
      (node (ref "RN12") (pin "7") (pinfunction "7_7") (pintype "input"))
      (node (ref "U1") (pin "103") (pinfunction "IO_103") (pintype "unspecified"))
    )
    (net (code "56") (name "/P1_IO7") (class "Default")
      (node (ref "RN12") (pin "6") (pinfunction "6_6") (pintype "input"))
      (node (ref "U1") (pin "102") (pinfunction "IO/DIFFIO_R3p_102") (pintype "unspecified"))
    )
    (net (code "57") (name "/P1_IO8") (class "Default")
      (node (ref "RN12") (pin "5") (pinfunction "5_5") (pintype "input"))
      (node (ref "U1") (pin "101") (pinfunction "IO/DIFFIO_R3n_101") (pintype "unspecified"))
    )
    (net (code "58") (name "/P2_IO1") (class "Default")
      (node (ref "RN15") (pin "8") (pinfunction "8_8") (pintype "input"))
      (node (ref "U1") (pin "98") (pinfunction "IO/DIFFIO_R4p_98") (pintype "unspecified"))
    )
    (net (code "59") (name "/P2_IO2") (class "Default")
      (node (ref "RN15") (pin "7") (pinfunction "7_7") (pintype "input"))
      (node (ref "U1") (pin "97") (pinfunction "IO/DIFFIO_R4n_97") (pintype "unspecified"))
    )
    (net (code "60") (name "/P2_IO3") (class "Default")
      (node (ref "RN15") (pin "6") (pinfunction "6_6") (pintype "input"))
      (node (ref "U1") (pin "96") (pinfunction "IO_96") (pintype "unspecified"))
    )
    (net (code "61") (name "/P2_IO4") (class "Default")
      (node (ref "RN15") (pin "5") (pinfunction "5_5") (pintype "input"))
      (node (ref "U1") (pin "95") (pinfunction "IO/DIFFIO_R5p_95") (pintype "unspecified"))
    )
    (net (code "62") (name "/P2_IO5") (class "Default")
      (node (ref "RN14") (pin "8") (pinfunction "8_8") (pintype "input"))
      (node (ref "U1") (pin "94") (pinfunction "IO/DIFFIO_R5n_94") (pintype "unspecified"))
    )
    (net (code "63") (name "/P2_IO6") (class "Default")
      (node (ref "RN14") (pin "7") (pinfunction "7_7") (pintype "input"))
      (node (ref "U1") (pin "93") (pinfunction "IO/DIFFIO_R6p_93") (pintype "unspecified"))
    )
    (net (code "64") (name "/P2_IO7") (class "Default")
      (node (ref "RN14") (pin "6") (pinfunction "6_6") (pintype "input"))
      (node (ref "U1") (pin "91") (pinfunction "IO/CLK3_91") (pintype "unspecified"))
    )
    (net (code "65") (name "/P2_IO8") (class "Default")
      (node (ref "RN14") (pin "5") (pinfunction "5_5") (pintype "input"))
      (node (ref "U1") (pin "89") (pinfunction "IO/CLK2_89") (pintype "unspecified"))
    )
    (net (code "66") (name "/PIN_109") (class "Default")
      (node (ref "R27") (pin "2") (pinfunction "2_2") (pintype "unspecified"))
      (node (ref "U1") (pin "109") (pinfunction "IO_109") (pintype "unspecified"))
    )
    (net (code "67") (name "/PIN_110") (class "Default")
      (node (ref "H2") (pin "33") (pinfunction "33_33") (pintype "unspecified"))
      (node (ref "U1") (pin "110") (pinfunction "IO/DIFFIO_T13n_110") (pintype "unspecified"))
    )
    (net (code "68") (name "/PIN_111") (class "Default")
      (node (ref "H2") (pin "34") (pinfunction "34_34") (pintype "unspecified"))
      (node (ref "U1") (pin "111") (pinfunction "IO/DIFFIO_T13p_111") (pintype "unspecified"))
    )
    (net (code "69") (name "/PIN_112") (class "Default")
      (node (ref "H2") (pin "31") (pinfunction "31_31") (pintype "unspecified"))
      (node (ref "U1") (pin "112") (pinfunction "IO/DIFFIO_T12n_112") (pintype "unspecified"))
    )
    (net (code "70") (name "/PIN_113") (class "Default")
      (node (ref "H2") (pin "32") (pinfunction "32_32") (pintype "unspecified"))
      (node (ref "U1") (pin "113") (pinfunction "IO/DIFFIO_T12p_113") (pintype "unspecified"))
    )
    (net (code "71") (name "/PIN_114") (class "Default")
      (node (ref "H2") (pin "29") (pinfunction "29_29") (pintype "unspecified"))
      (node (ref "U1") (pin "114") (pinfunction "IO/DIFFIO_T11n_114") (pintype "unspecified"))
    )
    (net (code "72") (name "/PIN_117") (class "Default")
      (node (ref "H2") (pin "30") (pinfunction "30_30") (pintype "unspecified"))
      (node (ref "U1") (pin "117") (pinfunction "IO/DIFFIO_T11p_117") (pintype "unspecified"))
    )
    (net (code "73") (name "/PIN_118") (class "Default")
      (node (ref "H2") (pin "27") (pinfunction "27_27") (pintype "unspecified"))
      (node (ref "U1") (pin "118") (pinfunction "IO_118") (pintype "unspecified"))
    )
    (net (code "74") (name "/PIN_119") (class "Default")
      (node (ref "H2") (pin "28") (pinfunction "28_28") (pintype "unspecified"))
      (node (ref "U1") (pin "119") (pinfunction "IO/DIFFIO_T10n_119") (pintype "unspecified"))
    )
    (net (code "75") (name "/PIN_120") (class "Default")
      (node (ref "H2") (pin "25") (pinfunction "25_25") (pintype "unspecified"))
      (node (ref "U1") (pin "120") (pinfunction "IO/DIFFIO_T10p_120") (pintype "unspecified"))
    )
    (net (code "76") (name "/PIN_121") (class "Default")
      (node (ref "H2") (pin "26") (pinfunction "26_26") (pintype "unspecified"))
      (node (ref "U1") (pin "121") (pinfunction "IO/DIFFIO_T9n_121") (pintype "unspecified"))
    )
    (net (code "77") (name "/PIN_122") (class "Default")
      (node (ref "H2") (pin "23") (pinfunction "23_23") (pintype "unspecified"))
      (node (ref "U1") (pin "122") (pinfunction "IO/DIFFIO_T9p_122") (pintype "unspecified"))
    )
    (net (code "78") (name "/PIN_123") (class "Default")
      (node (ref "H2") (pin "24") (pinfunction "24_24") (pintype "unspecified"))
      (node (ref "U1") (pin "123") (pinfunction "IO/DIFFIO_T8n_123") (pintype "unspecified"))
    )
    (net (code "79") (name "/PIN_124") (class "Default")
      (node (ref "H2") (pin "21") (pinfunction "21_21") (pintype "unspecified"))
      (node (ref "U1") (pin "124") (pinfunction "IO/DIFFIO_T8p_124") (pintype "unspecified"))
    )
    (net (code "80") (name "/PIN_125") (class "Default")
      (node (ref "H2") (pin "22") (pinfunction "22_22") (pintype "unspecified"))
      (node (ref "U1") (pin "125") (pinfunction "IO/DIFFIO_T7n_125") (pintype "unspecified"))
    )
    (net (code "81") (name "/PIN_127") (class "Default")
      (node (ref "H2") (pin "19") (pinfunction "19_19") (pintype "unspecified"))
      (node (ref "U1") (pin "127") (pinfunction "IO/DIFFIO_T7p_127") (pintype "unspecified"))
    )
    (net (code "82") (name "/PIN_129") (class "Default")
      (node (ref "H2") (pin "20") (pinfunction "20_20") (pintype "unspecified"))
      (node (ref "U1") (pin "129") (pinfunction "IO/DIFFIO_T6n_129") (pintype "unspecified"))
    )
    (net (code "83") (name "/PIN_130") (class "Default")
      (node (ref "H2") (pin "17") (pinfunction "17_17") (pintype "unspecified"))
      (node (ref "U1") (pin "130") (pinfunction "IO/DIFFIO_T6p_130") (pintype "unspecified"))
    )
    (net (code "84") (name "/PIN_131") (class "Default")
      (node (ref "H2") (pin "18") (pinfunction "18_18") (pintype "unspecified"))
      (node (ref "U1") (pin "131") (pinfunction "IO/DIFFIO_T5n_131") (pintype "unspecified"))
    )
    (net (code "85") (name "/PIN_132") (class "Default")
      (node (ref "H2") (pin "15") (pinfunction "15_15") (pintype "unspecified"))
      (node (ref "U1") (pin "132") (pinfunction "IO/DIFFIO_T5p_132") (pintype "unspecified"))
    )
    (net (code "86") (name "/PIN_133") (class "Default")
      (node (ref "H2") (pin "16") (pinfunction "16_16") (pintype "unspecified"))
      (node (ref "U1") (pin "133") (pinfunction "IO/DIFFIO_T4n_133") (pintype "unspecified"))
    )
    (net (code "87") (name "/PIN_134") (class "Default")
      (node (ref "H2") (pin "13") (pinfunction "13_13") (pintype "unspecified"))
      (node (ref "U1") (pin "134") (pinfunction "IO/DIFFIO_T4p_134") (pintype "unspecified"))
    )
    (net (code "88") (name "/PIN_138") (class "Default")
      (node (ref "H2") (pin "14") (pinfunction "14_14") (pintype "unspecified"))
      (node (ref "U1") (pin "138") (pinfunction "IO/DIFFIO_T3n_138") (pintype "unspecified"))
    )
    (net (code "89") (name "/PIN_139") (class "Default")
      (node (ref "H2") (pin "11") (pinfunction "11_11") (pintype "unspecified"))
      (node (ref "U1") (pin "139") (pinfunction "IO/DIFFIO_T3p_139") (pintype "unspecified"))
    )
    (net (code "90") (name "/PIN_140") (class "Default")
      (node (ref "H2") (pin "12") (pinfunction "12_12") (pintype "unspecified"))
      (node (ref "U1") (pin "140") (pinfunction "IO/DIFFIO_T2n_140") (pintype "unspecified"))
    )
    (net (code "91") (name "/PIN_141") (class "Default")
      (node (ref "H2") (pin "9") (pinfunction "9_9") (pintype "unspecified"))
      (node (ref "U1") (pin "141") (pinfunction "IO/DIFFIO_T2p_141") (pintype "unspecified"))
    )
    (net (code "92") (name "/PIN_142") (class "Default")
      (node (ref "H2") (pin "10") (pinfunction "10_10") (pintype "unspecified"))
      (node (ref "U1") (pin "142") (pinfunction "IO/DIFFIO_T1n_142") (pintype "unspecified"))
    )
    (net (code "93") (name "/PIN_143") (class "Default")
      (node (ref "H2") (pin "7") (pinfunction "7_7") (pintype "unspecified"))
      (node (ref "U1") (pin "143") (pinfunction "IO/DIFFIO_T1p_143") (pintype "unspecified"))
    )
    (net (code "94") (name "/PIN_144") (class "Default")
      (node (ref "H2") (pin "8") (pinfunction "8_8") (pintype "unspecified"))
      (node (ref "U1") (pin "144") (pinfunction "IO_144") (pintype "unspecified"))
    )
    (net (code "95") (name "/SW0") (class "Default")
      (node (ref "RN1") (pin "8") (pinfunction "8_8") (pintype "input"))
      (node (ref "U1") (pin "84") (pinfunction "IO/DIFFIO_R8n_84") (pintype "unspecified"))
    )
    (net (code "96") (name "/SW1") (class "Default")
      (node (ref "RN1") (pin "7") (pinfunction "7_7") (pintype "input"))
      (node (ref "U1") (pin "81") (pinfunction "IO_81") (pintype "unspecified"))
    )
    (net (code "97") (name "/SW2") (class "Default")
      (node (ref "RN1") (pin "6") (pinfunction "6_6") (pintype "input"))
      (node (ref "U1") (pin "80") (pinfunction "IO/DIFFIO_R9p_80") (pintype "unspecified"))
    )
    (net (code "98") (name "/SW3") (class "Default")
      (node (ref "RN1") (pin "5") (pinfunction "5_5") (pintype "input"))
      (node (ref "U1") (pin "79") (pinfunction "IO/DIFFIO_R9n_79") (pintype "unspecified"))
    )
    (net (code "99") (name "/SW4") (class "Default")
      (node (ref "RN2") (pin "8") (pinfunction "8_8") (pintype "input"))
      (node (ref "U1") (pin "78") (pinfunction "IO/DIFFIO_R10p_78") (pintype "unspecified"))
    )
    (net (code "100") (name "/SW5") (class "Default")
      (node (ref "RN2") (pin "7") (pinfunction "7_7") (pintype "input"))
      (node (ref "U1") (pin "77") (pinfunction "IO/DIFFIO_R10n_77") (pintype "unspecified"))
    )
    (net (code "101") (name "/SW6") (class "Default")
      (node (ref "RN2") (pin "6") (pinfunction "6_6") (pintype "input"))
      (node (ref "U1") (pin "76") (pinfunction "IO/DIFFIO_R11p_76") (pintype "unspecified"))
    )
    (net (code "102") (name "/SW7") (class "Default")
      (node (ref "RN2") (pin "5") (pinfunction "5_5") (pintype "input"))
      (node (ref "U1") (pin "75") (pinfunction "IO/DIFFIO_R11n_75") (pintype "unspecified"))
    )
    (net (code "103") (name "/SW8") (class "Default")
      (node (ref "RN3") (pin "8") (pinfunction "8_8") (pintype "input"))
      (node (ref "U1") (pin "74") (pinfunction "IO/DIFFIO_R12p_74") (pintype "unspecified"))
    )
    (net (code "104") (name "/SW9") (class "Default")
      (node (ref "RN3") (pin "7") (pinfunction "7_7") (pintype "input"))
      (node (ref "U1") (pin "73") (pinfunction "IO/DIFFIO_R12n_73") (pintype "unspecified"))
    )
    (net (code "105") (name "/TCK") (class "Default")
      (node (ref "H1") (pin "1") (pinfunction "1_1") (pintype "input"))
      (node (ref "U1") (pin "35") (pinfunction "TCK_35") (pintype "unspecified"))
    )
    (net (code "106") (name "/TDI") (class "Default")
      (node (ref "H1") (pin "9") (pinfunction "9_9") (pintype "input"))
      (node (ref "U1") (pin "34") (pinfunction "TDI_34") (pintype "unspecified"))
    )
    (net (code "107") (name "/TDO") (class "Default")
      (node (ref "H1") (pin "3") (pinfunction "3_3") (pintype "input"))
      (node (ref "U1") (pin "36") (pinfunction "TDO_36") (pintype "unspecified"))
    )
    (net (code "108") (name "/TMS") (class "Default")
      (node (ref "H1") (pin "5") (pinfunction "5_5") (pintype "input"))
      (node (ref "U1") (pin "33") (pinfunction "TMS_33") (pintype "unspecified"))
    )
    (net (code "109") (name "1.8V") (class "Default")
      (node (ref "1.8V") (pin "1") (pinfunction "1_1") (pintype "unspecified"))
      (node (ref "C14") (pin "2") (pinfunction "2_2") (pintype "unspecified"))
      (node (ref "C15") (pin "2") (pinfunction "2_2") (pintype "unspecified"))
      (node (ref "C16") (pin "2") (pinfunction "2_2") (pintype "unspecified"))
      (node (ref "C17") (pin "2") (pinfunction "2_2") (pintype "unspecified"))
      (node (ref "C5") (pin "2") (pinfunction "2_2") (pintype "input"))
      (node (ref "U1") (pin "126") (pinfunction "VCCINT_126") (pintype "unspecified"))
      (node (ref "U1") (pin "19") (pinfunction "VCCINT_19") (pintype "unspecified"))
      (node (ref "U1") (pin "56") (pinfunction "VCCINT_56") (pintype "unspecified"))
      (node (ref "U1") (pin "90") (pinfunction "VCCINT_90") (pintype "unspecified"))
      (node (ref "U3") (pin "5") (pinfunction "VOUT_5") (pintype "unspecified"))
    )
    (net (code "110") (name "3.3V") (class "Default")
      (node (ref "3.3V") (pin "1") (pinfunction "1_1") (pintype "unspecified"))
      (node (ref "BUZZER1") (pin "1") (pinfunction "+_1") (pintype "unspecified"))
      (node (ref "C10") (pin "2") (pinfunction "2_2") (pintype "unspecified"))
      (node (ref "C11") (pin "2") (pinfunction "2_2") (pintype "unspecified"))
      (node (ref "C12") (pin "2") (pinfunction "2_2") (pintype "unspecified"))
      (node (ref "C13") (pin "2") (pinfunction "2_2") (pintype "unspecified"))
      (node (ref "C18") (pin "2") (pinfunction "2_2") (pintype "unspecified"))
      (node (ref "C2") (pin "2") (pinfunction "2_2") (pintype "input"))
      (node (ref "C3") (pin "2") (pinfunction "2_2") (pintype "unspecified"))
      (node (ref "C4") (pin "2") (pinfunction "2_2") (pintype "input"))
      (node (ref "C6") (pin "2") (pinfunction "2_2") (pintype "unspecified"))
      (node (ref "C7") (pin "2") (pinfunction "2_2") (pintype "unspecified"))
      (node (ref "C8") (pin "2") (pinfunction "2_2") (pintype "unspecified"))
      (node (ref "C9") (pin "2") (pinfunction "2_2") (pintype "unspecified"))
      (node (ref "D2") (pin "1") (pinfunction "C_1") (pintype "input"))
      (node (ref "H1") (pin "4") (pinfunction "4_4") (pintype "input"))
      (node (ref "H2") (pin "37") (pinfunction "37_37") (pintype "unspecified"))
      (node (ref "H2") (pin "38") (pinfunction "38_38") (pintype "unspecified"))
      (node (ref "H2") (pin "5") (pinfunction "5_5") (pintype "unspecified"))
      (node (ref "H2") (pin "6") (pinfunction "6_6") (pintype "unspecified"))
      (node (ref "H3") (pin "11") (pinfunction "11_11") (pintype "unspecified"))
      (node (ref "H3") (pin "12") (pinfunction "12_12") (pintype "unspecified"))
      (node (ref "H4") (pin "11") (pinfunction "11_11") (pintype "unspecified"))
      (node (ref "H4") (pin "12") (pinfunction "12_12") (pintype "unspecified"))
      (node (ref "OSC1") (pin "1") (pinfunction "Tri-state_1") (pintype "unspecified"))
      (node (ref "OSC1") (pin "4") (pinfunction "VDD_4") (pintype "unspecified"))
      (node (ref "R10") (pin "2") (pinfunction "2_2") (pintype "unspecified"))
      (node (ref "R28") (pin "2") (pinfunction "2_2") (pintype "unspecified"))
      (node (ref "R29") (pin "2") (pinfunction "2_2") (pintype "unspecified"))
      (node (ref "R31") (pin "2") (pinfunction "2_2") (pintype "unspecified"))
      (node (ref "SW0") (pin "3") (pinfunction "3_3") (pintype "unspecified"))
      (node (ref "SW1") (pin "3") (pinfunction "3_3") (pintype "unspecified"))
      (node (ref "SW2") (pin "3") (pinfunction "3_3") (pintype "unspecified"))
      (node (ref "SW3") (pin "3") (pinfunction "3_3") (pintype "unspecified"))
      (node (ref "SW4") (pin "3") (pinfunction "3_3") (pintype "unspecified"))
      (node (ref "SW5") (pin "3") (pinfunction "3_3") (pintype "unspecified"))
      (node (ref "SW6") (pin "3") (pinfunction "3_3") (pintype "unspecified"))
      (node (ref "SW7") (pin "3") (pinfunction "3_3") (pintype "unspecified"))
      (node (ref "SW8") (pin "3") (pinfunction "3_3") (pintype "unspecified"))
      (node (ref "SW9") (pin "3") (pinfunction "3_3") (pintype "unspecified"))
      (node (ref "U1") (pin "100") (pinfunction "VCCIO2_100") (pintype "unspecified"))
      (node (ref "U1") (pin "116") (pinfunction "VCCIO2_116") (pintype "unspecified"))
      (node (ref "U1") (pin "136") (pinfunction "VCCIO2_136") (pintype "unspecified"))
      (node (ref "U1") (pin "25") (pinfunction "VCCIO1_25") (pintype "unspecified"))
      (node (ref "U1") (pin "46") (pinfunction "VCCIO1_46") (pintype "unspecified"))
      (node (ref "U1") (pin "64") (pinfunction "VCCIO1_64") (pintype "unspecified"))
      (node (ref "U1") (pin "82") (pinfunction "VCCIO2_82") (pintype "unspecified"))
      (node (ref "U1") (pin "9") (pinfunction "VCCIO1_9") (pintype "unspecified"))
      (node (ref "U2") (pin "5") (pinfunction "VOUT_5") (pintype "unspecified"))
      (node (ref "U3") (pin "1") (pinfunction "VIN_1") (pintype "unspecified"))
      (node (ref "U3") (pin "3") (pinfunction "EN_3") (pintype "unspecified"))
    )
    (net (code "111") (name "GND") (class "Default")
      (node (ref "C0") (pin "1") (pinfunction "1_1") (pintype "unspecified"))
      (node (ref "C1") (pin "1") (pinfunction "1_1") (pintype "input"))
      (node (ref "C10") (pin "1") (pinfunction "1_1") (pintype "unspecified"))
      (node (ref "C11") (pin "1") (pinfunction "1_1") (pintype "unspecified"))
      (node (ref "C12") (pin "1") (pinfunction "1_1") (pintype "unspecified"))
      (node (ref "C13") (pin "1") (pinfunction "1_1") (pintype "unspecified"))
      (node (ref "C14") (pin "1") (pinfunction "1_1") (pintype "unspecified"))
      (node (ref "C15") (pin "1") (pinfunction "1_1") (pintype "unspecified"))
      (node (ref "C16") (pin "1") (pinfunction "1_1") (pintype "unspecified"))
      (node (ref "C17") (pin "1") (pinfunction "1_1") (pintype "unspecified"))
      (node (ref "C18") (pin "1") (pinfunction "1_1") (pintype "unspecified"))
      (node (ref "C2") (pin "1") (pinfunction "1_1") (pintype "input"))
      (node (ref "C3") (pin "1") (pinfunction "1_1") (pintype "unspecified"))
      (node (ref "C4") (pin "1") (pinfunction "1_1") (pintype "input"))
      (node (ref "C5") (pin "1") (pinfunction "1_1") (pintype "input"))
      (node (ref "C6") (pin "1") (pinfunction "1_1") (pintype "unspecified"))
      (node (ref "C7") (pin "1") (pinfunction "1_1") (pintype "unspecified"))
      (node (ref "C8") (pin "1") (pinfunction "1_1") (pintype "unspecified"))
      (node (ref "C9") (pin "1") (pinfunction "1_1") (pintype "unspecified"))
      (node (ref "D1") (pin "2") (pinfunction "A_2") (pintype "unspecified"))
      (node (ref "H1") (pin "10") (pinfunction "10_10") (pintype "input"))
      (node (ref "H1") (pin "2") (pinfunction "2_2") (pintype "input"))
      (node (ref "H2") (pin "3") (pinfunction "3_3") (pintype "unspecified"))
      (node (ref "H2") (pin "35") (pinfunction "35_35") (pintype "unspecified"))
      (node (ref "H2") (pin "36") (pinfunction "36_36") (pintype "unspecified"))
      (node (ref "H2") (pin "39") (pinfunction "39_39") (pintype "unspecified"))
      (node (ref "H2") (pin "4") (pinfunction "4_4") (pintype "unspecified"))
      (node (ref "H2") (pin "40") (pinfunction "40_40") (pintype "unspecified"))
      (node (ref "H3") (pin "10") (pinfunction "10_10") (pintype "unspecified"))
      (node (ref "H3") (pin "9") (pinfunction "9_9") (pintype "unspecified"))
      (node (ref "H4") (pin "10") (pinfunction "10_10") (pintype "unspecified"))
      (node (ref "H4") (pin "9") (pinfunction "9_9") (pintype "unspecified"))
      (node (ref "HEX0") (pin "1") (pinfunction "COM_1") (pintype "unspecified"))
      (node (ref "HEX0") (pin "6") (pinfunction "COM_6") (pintype "unspecified"))
      (node (ref "HEX1") (pin "1") (pinfunction "COM_1") (pintype "unspecified"))
      (node (ref "HEX1") (pin "6") (pinfunction "COM_6") (pintype "unspecified"))
      (node (ref "HEX2") (pin "1") (pinfunction "COM_1") (pintype "unspecified"))
      (node (ref "HEX2") (pin "6") (pinfunction "COM_6") (pintype "unspecified"))
      (node (ref "HEX3") (pin "1") (pinfunction "COM_1") (pintype "unspecified"))
      (node (ref "HEX3") (pin "6") (pinfunction "COM_6") (pintype "unspecified"))
      (node (ref "KEY0") (pin "4") (pinfunction "D_4") (pintype "unspecified"))
      (node (ref "KEY1") (pin "4") (pinfunction "D_4") (pintype "unspecified"))
      (node (ref "KEY2") (pin "4") (pinfunction "D_4") (pintype "unspecified"))
      (node (ref "KEY3") (pin "4") (pinfunction "D_4") (pintype "unspecified"))
      (node (ref "OSC1") (pin "2") (pinfunction "GND_2") (pintype "unspecified"))
      (node (ref "Q1") (pin "2") (pinfunction "2_2") (pintype "input"))
      (node (ref "R0") (pin "1") (pinfunction "1_1") (pintype "unspecified"))
      (node (ref "R1") (pin "1") (pinfunction "1_1") (pintype "unspecified"))
      (node (ref "R2") (pin "1") (pinfunction "1_1") (pintype "unspecified"))
      (node (ref "R20") (pin "1") (pinfunction "1_1") (pintype "input"))
      (node (ref "R21") (pin "1") (pinfunction "1_1") (pintype "input"))
      (node (ref "R22") (pin "1") (pinfunction "1_1") (pintype "unspecified"))
      (node (ref "R3") (pin "1") (pinfunction "1_1") (pintype "unspecified"))
      (node (ref "R4") (pin "1") (pinfunction "1_1") (pintype "unspecified"))
      (node (ref "R5") (pin "1") (pinfunction "1_1") (pintype "unspecified"))
      (node (ref "R6") (pin "1") (pinfunction "1_1") (pintype "unspecified"))
      (node (ref "R7") (pin "1") (pinfunction "1_1") (pintype "unspecified"))
      (node (ref "R8") (pin "1") (pinfunction "1_1") (pintype "unspecified"))
      (node (ref "R9") (pin "1") (pinfunction "1_1") (pintype "unspecified"))
      (node (ref "SW0") (pin "1") (pinfunction "1_1") (pintype "unspecified"))
      (node (ref "SW1") (pin "1") (pinfunction "1_1") (pintype "unspecified"))
      (node (ref "SW2") (pin "1") (pinfunction "1_1") (pintype "unspecified"))
      (node (ref "SW3") (pin "1") (pinfunction "1_1") (pintype "unspecified"))
      (node (ref "SW4") (pin "1") (pinfunction "1_1") (pintype "unspecified"))
      (node (ref "SW5") (pin "1") (pinfunction "1_1") (pintype "unspecified"))
      (node (ref "SW6") (pin "1") (pinfunction "1_1") (pintype "unspecified"))
      (node (ref "SW7") (pin "1") (pinfunction "1_1") (pintype "unspecified"))
      (node (ref "SW8") (pin "1") (pinfunction "1_1") (pintype "unspecified"))
      (node (ref "SW9") (pin "1") (pinfunction "1_1") (pintype "unspecified"))
      (node (ref "U1") (pin "10") (pinfunction "GND_10") (pintype "unspecified"))
      (node (ref "U1") (pin "115") (pinfunction "GND_115") (pintype "unspecified"))
      (node (ref "U1") (pin "128") (pinfunction "GND_128") (pintype "unspecified"))
      (node (ref "U1") (pin "135") (pinfunction "GND_135") (pintype "unspecified"))
      (node (ref "U1") (pin "137") (pinfunction "GND_137") (pintype "unspecified"))
      (node (ref "U1") (pin "17") (pinfunction "GND_17") (pintype "unspecified"))
      (node (ref "U1") (pin "26") (pinfunction "GND_26") (pintype "unspecified"))
      (node (ref "U1") (pin "47") (pinfunction "GND_47") (pintype "unspecified"))
      (node (ref "U1") (pin "54") (pinfunction "GND_54") (pintype "unspecified"))
      (node (ref "U1") (pin "65") (pinfunction "GND_65") (pintype "unspecified"))
      (node (ref "U1") (pin "8") (pinfunction "GND_8") (pintype "unspecified"))
      (node (ref "U1") (pin "83") (pinfunction "GND_83") (pintype "unspecified"))
      (node (ref "U1") (pin "92") (pinfunction "GND_92") (pintype "unspecified"))
      (node (ref "U1") (pin "99") (pinfunction "GND_99") (pintype "unspecified"))
      (node (ref "U2") (pin "2") (pinfunction "GND_2") (pintype "unspecified"))
      (node (ref "U3") (pin "2") (pinfunction "GND_2") (pintype "unspecified"))
      (node (ref "U6") (pin "A12") (pinfunction "GND_A12") (pintype "unspecified"))
      (node (ref "U6") (pin "B12") (pinfunction "GND_B12") (pintype "unspecified"))
    )
    (net (code "112") (name "Net-(BUZZER1--)") (class "Default")
      (node (ref "BUZZER1") (pin "2") (pinfunction "-_2") (pintype "unspecified"))
      (node (ref "D2") (pin "2") (pinfunction "A_2") (pintype "input"))
      (node (ref "Q1") (pin "3") (pinfunction "3_3") (pintype "input"))
    )
    (net (code "113") (name "Net-(H3-Pad1)") (class "Default")
      (node (ref "H3") (pin "1") (pinfunction "1_1") (pintype "unspecified"))
      (node (ref "RN13") (pin "1") (pinfunction "1_1") (pintype "input"))
    )
    (net (code "114") (name "Net-(H3-Pad2)") (class "Default")
      (node (ref "H3") (pin "2") (pinfunction "2_2") (pintype "unspecified"))
      (node (ref "RN13") (pin "2") (pinfunction "2_2") (pintype "input"))
    )
    (net (code "115") (name "Net-(H3-Pad3)") (class "Default")
      (node (ref "H3") (pin "3") (pinfunction "3_3") (pintype "unspecified"))
      (node (ref "RN13") (pin "3") (pinfunction "3_3") (pintype "input"))
    )
    (net (code "116") (name "Net-(H3-Pad4)") (class "Default")
      (node (ref "H3") (pin "4") (pinfunction "4_4") (pintype "unspecified"))
      (node (ref "RN13") (pin "4") (pinfunction "4_4") (pintype "input"))
    )
    (net (code "117") (name "Net-(H3-Pad5)") (class "Default")
      (node (ref "H3") (pin "5") (pinfunction "5_5") (pintype "unspecified"))
      (node (ref "RN12") (pin "1") (pinfunction "1_1") (pintype "input"))
    )
    (net (code "118") (name "Net-(H3-Pad6)") (class "Default")
      (node (ref "H3") (pin "6") (pinfunction "6_6") (pintype "unspecified"))
      (node (ref "RN12") (pin "2") (pinfunction "2_2") (pintype "input"))
    )
    (net (code "119") (name "Net-(H3-Pad7)") (class "Default")
      (node (ref "H3") (pin "7") (pinfunction "7_7") (pintype "unspecified"))
      (node (ref "RN12") (pin "3") (pinfunction "3_3") (pintype "input"))
    )
    (net (code "120") (name "Net-(H3-Pad8)") (class "Default")
      (node (ref "H3") (pin "8") (pinfunction "8_8") (pintype "unspecified"))
      (node (ref "RN12") (pin "4") (pinfunction "4_4") (pintype "input"))
    )
    (net (code "121") (name "Net-(H4-Pad1)") (class "Default")
      (node (ref "H4") (pin "1") (pinfunction "1_1") (pintype "unspecified"))
      (node (ref "RN15") (pin "1") (pinfunction "1_1") (pintype "input"))
    )
    (net (code "122") (name "Net-(H4-Pad2)") (class "Default")
      (node (ref "H4") (pin "2") (pinfunction "2_2") (pintype "unspecified"))
      (node (ref "RN15") (pin "2") (pinfunction "2_2") (pintype "input"))
    )
    (net (code "123") (name "Net-(H4-Pad3)") (class "Default")
      (node (ref "H4") (pin "3") (pinfunction "3_3") (pintype "unspecified"))
      (node (ref "RN15") (pin "3") (pinfunction "3_3") (pintype "input"))
    )
    (net (code "124") (name "Net-(H4-Pad4)") (class "Default")
      (node (ref "H4") (pin "4") (pinfunction "4_4") (pintype "unspecified"))
      (node (ref "RN15") (pin "4") (pinfunction "4_4") (pintype "input"))
    )
    (net (code "125") (name "Net-(H4-Pad5)") (class "Default")
      (node (ref "H4") (pin "5") (pinfunction "5_5") (pintype "unspecified"))
      (node (ref "RN14") (pin "1") (pinfunction "1_1") (pintype "input"))
    )
    (net (code "126") (name "Net-(H4-Pad6)") (class "Default")
      (node (ref "H4") (pin "6") (pinfunction "6_6") (pintype "unspecified"))
      (node (ref "RN14") (pin "2") (pinfunction "2_2") (pintype "input"))
    )
    (net (code "127") (name "Net-(H4-Pad7)") (class "Default")
      (node (ref "H4") (pin "7") (pinfunction "7_7") (pintype "unspecified"))
      (node (ref "RN14") (pin "3") (pinfunction "3_3") (pintype "input"))
    )
    (net (code "128") (name "Net-(H4-Pad8)") (class "Default")
      (node (ref "H4") (pin "8") (pinfunction "8_8") (pintype "unspecified"))
      (node (ref "RN14") (pin "4") (pinfunction "4_4") (pintype "input"))
    )
    (net (code "129") (name "Net-(HEX0-A)") (class "Default")
      (node (ref "HEX0") (pin "10") (pinfunction "A_10") (pintype "unspecified"))
      (node (ref "RN4") (pin "1") (pinfunction "1_1") (pintype "input"))
    )
    (net (code "130") (name "Net-(HEX0-B)") (class "Default")
      (node (ref "HEX0") (pin "9") (pinfunction "B_9") (pintype "unspecified"))
      (node (ref "RN4") (pin "2") (pinfunction "2_2") (pintype "input"))
    )
    (net (code "131") (name "Net-(HEX0-C)") (class "Default")
      (node (ref "HEX0") (pin "8") (pinfunction "C_8") (pintype "unspecified"))
      (node (ref "RN4") (pin "3") (pinfunction "3_3") (pintype "input"))
    )
    (net (code "132") (name "Net-(HEX0-D)") (class "Default")
      (node (ref "HEX0") (pin "5") (pinfunction "D_5") (pintype "unspecified"))
      (node (ref "RN5") (pin "1") (pinfunction "1_1") (pintype "input"))
    )
    (net (code "133") (name "Net-(HEX0-DP)") (class "Default")
      (node (ref "HEX0") (pin "7") (pinfunction "DP_7") (pintype "unspecified"))
      (node (ref "RN4") (pin "4") (pinfunction "4_4") (pintype "input"))
    )
    (net (code "134") (name "Net-(HEX0-E)") (class "Default")
      (node (ref "HEX0") (pin "4") (pinfunction "E_4") (pintype "unspecified"))
      (node (ref "RN5") (pin "2") (pinfunction "2_2") (pintype "input"))
    )
    (net (code "135") (name "Net-(HEX0-F)") (class "Default")
      (node (ref "HEX0") (pin "2") (pinfunction "F_2") (pintype "unspecified"))
      (node (ref "RN5") (pin "4") (pinfunction "4_4") (pintype "input"))
    )
    (net (code "136") (name "Net-(HEX0-G)") (class "Default")
      (node (ref "HEX0") (pin "3") (pinfunction "G_3") (pintype "unspecified"))
      (node (ref "RN5") (pin "3") (pinfunction "3_3") (pintype "input"))
    )
    (net (code "137") (name "Net-(HEX1-A)") (class "Default")
      (node (ref "HEX1") (pin "10") (pinfunction "A_10") (pintype "unspecified"))
      (node (ref "RN6") (pin "1") (pinfunction "1_1") (pintype "input"))
    )
    (net (code "138") (name "Net-(HEX1-B)") (class "Default")
      (node (ref "HEX1") (pin "9") (pinfunction "B_9") (pintype "unspecified"))
      (node (ref "RN6") (pin "2") (pinfunction "2_2") (pintype "input"))
    )
    (net (code "139") (name "Net-(HEX1-C)") (class "Default")
      (node (ref "HEX1") (pin "8") (pinfunction "C_8") (pintype "unspecified"))
      (node (ref "RN6") (pin "3") (pinfunction "3_3") (pintype "input"))
    )
    (net (code "140") (name "Net-(HEX1-D)") (class "Default")
      (node (ref "HEX1") (pin "5") (pinfunction "D_5") (pintype "unspecified"))
      (node (ref "RN7") (pin "1") (pinfunction "1_1") (pintype "input"))
    )
    (net (code "141") (name "Net-(HEX1-DP)") (class "Default")
      (node (ref "HEX1") (pin "7") (pinfunction "DP_7") (pintype "unspecified"))
      (node (ref "RN6") (pin "4") (pinfunction "4_4") (pintype "input"))
    )
    (net (code "142") (name "Net-(HEX1-E)") (class "Default")
      (node (ref "HEX1") (pin "4") (pinfunction "E_4") (pintype "unspecified"))
      (node (ref "RN7") (pin "2") (pinfunction "2_2") (pintype "input"))
    )
    (net (code "143") (name "Net-(HEX1-F)") (class "Default")
      (node (ref "HEX1") (pin "2") (pinfunction "F_2") (pintype "unspecified"))
      (node (ref "RN7") (pin "4") (pinfunction "4_4") (pintype "input"))
    )
    (net (code "144") (name "Net-(HEX1-G)") (class "Default")
      (node (ref "HEX1") (pin "3") (pinfunction "G_3") (pintype "unspecified"))
      (node (ref "RN7") (pin "3") (pinfunction "3_3") (pintype "input"))
    )
    (net (code "145") (name "Net-(HEX2-A)") (class "Default")
      (node (ref "HEX2") (pin "10") (pinfunction "A_10") (pintype "unspecified"))
      (node (ref "RN8") (pin "1") (pinfunction "1_1") (pintype "input"))
    )
    (net (code "146") (name "Net-(HEX2-B)") (class "Default")
      (node (ref "HEX2") (pin "9") (pinfunction "B_9") (pintype "unspecified"))
      (node (ref "RN8") (pin "2") (pinfunction "2_2") (pintype "input"))
    )
    (net (code "147") (name "Net-(HEX2-C)") (class "Default")
      (node (ref "HEX2") (pin "8") (pinfunction "C_8") (pintype "unspecified"))
      (node (ref "RN8") (pin "3") (pinfunction "3_3") (pintype "input"))
    )
    (net (code "148") (name "Net-(HEX2-D)") (class "Default")
      (node (ref "HEX2") (pin "5") (pinfunction "D_5") (pintype "unspecified"))
      (node (ref "RN9") (pin "1") (pinfunction "1_1") (pintype "input"))
    )
    (net (code "149") (name "Net-(HEX2-DP)") (class "Default")
      (node (ref "HEX2") (pin "7") (pinfunction "DP_7") (pintype "unspecified"))
      (node (ref "RN8") (pin "4") (pinfunction "4_4") (pintype "input"))
    )
    (net (code "150") (name "Net-(HEX2-E)") (class "Default")
      (node (ref "HEX2") (pin "4") (pinfunction "E_4") (pintype "unspecified"))
      (node (ref "RN9") (pin "2") (pinfunction "2_2") (pintype "input"))
    )
    (net (code "151") (name "Net-(HEX2-F)") (class "Default")
      (node (ref "HEX2") (pin "2") (pinfunction "F_2") (pintype "unspecified"))
      (node (ref "RN9") (pin "4") (pinfunction "4_4") (pintype "input"))
    )
    (net (code "152") (name "Net-(HEX2-G)") (class "Default")
      (node (ref "HEX2") (pin "3") (pinfunction "G_3") (pintype "unspecified"))
      (node (ref "RN9") (pin "3") (pinfunction "3_3") (pintype "input"))
    )
    (net (code "153") (name "Net-(HEX3-A)") (class "Default")
      (node (ref "HEX3") (pin "10") (pinfunction "A_10") (pintype "unspecified"))
      (node (ref "RN10") (pin "1") (pinfunction "1_1") (pintype "input"))
    )
    (net (code "154") (name "Net-(HEX3-B)") (class "Default")
      (node (ref "HEX3") (pin "9") (pinfunction "B_9") (pintype "unspecified"))
      (node (ref "RN10") (pin "2") (pinfunction "2_2") (pintype "input"))
    )
    (net (code "155") (name "Net-(HEX3-C)") (class "Default")
      (node (ref "HEX3") (pin "8") (pinfunction "C_8") (pintype "unspecified"))
      (node (ref "RN10") (pin "3") (pinfunction "3_3") (pintype "input"))
    )
    (net (code "156") (name "Net-(HEX3-D)") (class "Default")
      (node (ref "HEX3") (pin "5") (pinfunction "D_5") (pintype "unspecified"))
      (node (ref "RN11") (pin "1") (pinfunction "1_1") (pintype "input"))
    )
    (net (code "157") (name "Net-(HEX3-DP)") (class "Default")
      (node (ref "HEX3") (pin "7") (pinfunction "DP_7") (pintype "unspecified"))
      (node (ref "RN10") (pin "4") (pinfunction "4_4") (pintype "input"))
    )
    (net (code "158") (name "Net-(HEX3-E)") (class "Default")
      (node (ref "HEX3") (pin "4") (pinfunction "E_4") (pintype "unspecified"))
      (node (ref "RN11") (pin "2") (pinfunction "2_2") (pintype "input"))
    )
    (net (code "159") (name "Net-(HEX3-F)") (class "Default")
      (node (ref "HEX3") (pin "2") (pinfunction "F_2") (pintype "unspecified"))
      (node (ref "RN11") (pin "4") (pinfunction "4_4") (pintype "input"))
    )
    (net (code "160") (name "Net-(HEX3-G)") (class "Default")
      (node (ref "HEX3") (pin "3") (pinfunction "G_3") (pintype "unspecified"))
      (node (ref "RN11") (pin "3") (pinfunction "3_3") (pintype "input"))
    )
    (net (code "161") (name "Net-(LED0--)") (class "Default")
      (node (ref "LED0") (pin "2") (pinfunction "-_2") (pintype "unspecified"))
      (node (ref "R0") (pin "2") (pinfunction "2_2") (pintype "unspecified"))
    )
    (net (code "162") (name "Net-(LED1--)") (class "Default")
      (node (ref "LED1") (pin "2") (pinfunction "-_2") (pintype "unspecified"))
      (node (ref "R1") (pin "2") (pinfunction "2_2") (pintype "unspecified"))
    )
    (net (code "163") (name "Net-(LED2--)") (class "Default")
      (node (ref "LED2") (pin "2") (pinfunction "-_2") (pintype "unspecified"))
      (node (ref "R2") (pin "2") (pinfunction "2_2") (pintype "unspecified"))
    )
    (net (code "164") (name "Net-(LED3--)") (class "Default")
      (node (ref "LED3") (pin "2") (pinfunction "-_2") (pintype "unspecified"))
      (node (ref "R3") (pin "2") (pinfunction "2_2") (pintype "unspecified"))
    )
    (net (code "165") (name "Net-(LED4--)") (class "Default")
      (node (ref "LED4") (pin "2") (pinfunction "-_2") (pintype "unspecified"))
      (node (ref "R4") (pin "2") (pinfunction "2_2") (pintype "unspecified"))
    )
    (net (code "166") (name "Net-(LED5--)") (class "Default")
      (node (ref "LED5") (pin "2") (pinfunction "-_2") (pintype "unspecified"))
      (node (ref "R5") (pin "2") (pinfunction "2_2") (pintype "unspecified"))
    )
    (net (code "167") (name "Net-(LED6--)") (class "Default")
      (node (ref "LED6") (pin "2") (pinfunction "-_2") (pintype "unspecified"))
      (node (ref "R6") (pin "2") (pinfunction "2_2") (pintype "unspecified"))
    )
    (net (code "168") (name "Net-(LED7--)") (class "Default")
      (node (ref "LED7") (pin "2") (pinfunction "-_2") (pintype "unspecified"))
      (node (ref "R7") (pin "2") (pinfunction "2_2") (pintype "unspecified"))
    )
    (net (code "169") (name "Net-(LED8--)") (class "Default")
      (node (ref "LED8") (pin "2") (pinfunction "-_2") (pintype "unspecified"))
      (node (ref "R8") (pin "2") (pinfunction "2_2") (pintype "unspecified"))
    )
    (net (code "170") (name "Net-(LED9--)") (class "Default")
      (node (ref "LED9") (pin "2") (pinfunction "-_2") (pintype "unspecified"))
      (node (ref "R9") (pin "2") (pinfunction "2_2") (pintype "unspecified"))
    )
    (net (code "171") (name "Net-(LED10--)") (class "Default")
      (node (ref "LED10") (pin "2") (pinfunction "-_2") (pintype "unspecified"))
      (node (ref "R22") (pin "2") (pinfunction "2_2") (pintype "unspecified"))
    )
    (net (code "172") (name "Net-(Q1-Pad1)") (class "Default")
      (node (ref "Q1") (pin "1") (pinfunction "1_1") (pintype "input"))
      (node (ref "R27") (pin "1") (pinfunction "1_1") (pintype "unspecified"))
    )
    (net (code "173") (name "Net-(RN1-Pad1)") (class "Default")
      (node (ref "RN1") (pin "1") (pinfunction "1_1") (pintype "input"))
      (node (ref "SW0") (pin "2") (pinfunction "2_2") (pintype "unspecified"))
    )
    (net (code "174") (name "Net-(RN1-Pad2)") (class "Default")
      (node (ref "RN1") (pin "2") (pinfunction "2_2") (pintype "input"))
      (node (ref "SW1") (pin "2") (pinfunction "2_2") (pintype "unspecified"))
    )
    (net (code "175") (name "Net-(RN1-Pad3)") (class "Default")
      (node (ref "RN1") (pin "3") (pinfunction "3_3") (pintype "input"))
      (node (ref "SW2") (pin "2") (pinfunction "2_2") (pintype "unspecified"))
    )
    (net (code "176") (name "Net-(RN1-Pad4)") (class "Default")
      (node (ref "RN1") (pin "4") (pinfunction "4_4") (pintype "input"))
      (node (ref "SW3") (pin "2") (pinfunction "2_2") (pintype "unspecified"))
    )
    (net (code "177") (name "Net-(RN2-Pad1)") (class "Default")
      (node (ref "RN2") (pin "1") (pinfunction "1_1") (pintype "input"))
      (node (ref "SW4") (pin "2") (pinfunction "2_2") (pintype "unspecified"))
    )
    (net (code "178") (name "Net-(RN2-Pad2)") (class "Default")
      (node (ref "RN2") (pin "2") (pinfunction "2_2") (pintype "input"))
      (node (ref "SW5") (pin "2") (pinfunction "2_2") (pintype "unspecified"))
    )
    (net (code "179") (name "Net-(RN2-Pad3)") (class "Default")
      (node (ref "RN2") (pin "3") (pinfunction "3_3") (pintype "input"))
      (node (ref "SW6") (pin "2") (pinfunction "2_2") (pintype "unspecified"))
    )
    (net (code "180") (name "Net-(RN2-Pad4)") (class "Default")
      (node (ref "RN2") (pin "4") (pinfunction "4_4") (pintype "input"))
      (node (ref "SW7") (pin "2") (pinfunction "2_2") (pintype "unspecified"))
    )
    (net (code "181") (name "Net-(RN3-Pad1)") (class "Default")
      (node (ref "RN3") (pin "1") (pinfunction "1_1") (pintype "input"))
      (node (ref "SW8") (pin "2") (pinfunction "2_2") (pintype "unspecified"))
    )
    (net (code "182") (name "Net-(RN3-Pad2)") (class "Default")
      (node (ref "RN3") (pin "2") (pinfunction "2_2") (pintype "input"))
      (node (ref "SW9") (pin "2") (pinfunction "2_2") (pintype "unspecified"))
    )
    (net (code "183") (name "Net-(U6-CC1)") (class "Default")
      (node (ref "R20") (pin "2") (pinfunction "2_2") (pintype "input"))
      (node (ref "U6") (pin "A5") (pinfunction "CC1_A5") (pintype "unspecified"))
    )
    (net (code "184") (name "Net-(U6-CC2)") (class "Default")
      (node (ref "R21") (pin "2") (pinfunction "2_2") (pintype "input"))
      (node (ref "U6") (pin "B5") (pinfunction "CC2_B5") (pintype "unspecified"))
    )
    (net (code "185") (name "VCC") (class "Default")
      (node (ref "SW17") (pin "3") (pinfunction "3_3") (pintype "unspecified"))
      (node (ref "U6") (pin "A9") (pinfunction "VBUS_A9") (pintype "unspecified"))
      (node (ref "U6") (pin "B9") (pinfunction "VBUS_B9") (pintype "unspecified"))
    )
    (net (code "186") (name "unconnected-(BUZZER1-Pad3)") (class "Default")
      (node (ref "BUZZER1") (pin "3") (pinfunction "3_3") (pintype "unspecified+no_connect"))
    )
    (net (code "187") (name "unconnected-(BUZZER1-Pad4)") (class "Default")
      (node (ref "BUZZER1") (pin "4") (pinfunction "4_4") (pintype "unspecified+no_connect"))
    )
    (net (code "188") (name "unconnected-(H1-Pad6)") (class "Default")
      (node (ref "H1") (pin "6") (pinfunction "6_6") (pintype "input+no_connect"))
    )
    (net (code "189") (name "unconnected-(H1-Pad7)") (class "Default")
      (node (ref "H1") (pin "7") (pinfunction "7_7") (pintype "input+no_connect"))
    )
    (net (code "190") (name "unconnected-(H1-Pad8)") (class "Default")
      (node (ref "H1") (pin "8") (pinfunction "8_8") (pintype "input+no_connect"))
    )
    (net (code "191") (name "unconnected-(KEY0-A-Pad1)") (class "Default")
      (node (ref "KEY0") (pin "1") (pinfunction "A_1") (pintype "unspecified"))
    )
    (net (code "192") (name "unconnected-(KEY0-C-Pad3)") (class "Default")
      (node (ref "KEY0") (pin "3") (pinfunction "C_3") (pintype "unspecified"))
    )
    (net (code "193") (name "unconnected-(KEY1-A-Pad1)") (class "Default")
      (node (ref "KEY1") (pin "1") (pinfunction "A_1") (pintype "unspecified"))
    )
    (net (code "194") (name "unconnected-(KEY1-C-Pad3)") (class "Default")
      (node (ref "KEY1") (pin "3") (pinfunction "C_3") (pintype "unspecified"))
    )
    (net (code "195") (name "unconnected-(KEY2-A-Pad1)") (class "Default")
      (node (ref "KEY2") (pin "1") (pinfunction "A_1") (pintype "unspecified"))
    )
    (net (code "196") (name "unconnected-(KEY2-C-Pad3)") (class "Default")
      (node (ref "KEY2") (pin "3") (pinfunction "C_3") (pintype "unspecified"))
    )
    (net (code "197") (name "unconnected-(KEY3-A-Pad1)") (class "Default")
      (node (ref "KEY3") (pin "1") (pinfunction "A_1") (pintype "unspecified"))
    )
    (net (code "198") (name "unconnected-(KEY3-C-Pad3)") (class "Default")
      (node (ref "KEY3") (pin "3") (pinfunction "C_3") (pintype "unspecified"))
    )
    (net (code "199") (name "unconnected-(RN3-Pad3)") (class "Default")
      (node (ref "RN3") (pin "3") (pinfunction "3_3") (pintype "input"))
    )
    (net (code "200") (name "unconnected-(RN3-Pad4)") (class "Default")
      (node (ref "RN3") (pin "4") (pinfunction "4_4") (pintype "input"))
    )
    (net (code "201") (name "unconnected-(RN3-Pad5)") (class "Default")
      (node (ref "RN3") (pin "5") (pinfunction "5_5") (pintype "input"))
    )
    (net (code "202") (name "unconnected-(RN3-Pad6)") (class "Default")
      (node (ref "RN3") (pin "6") (pinfunction "6_6") (pintype "input"))
    )
    (net (code "203") (name "unconnected-(SW0-Pad4)") (class "Default")
      (node (ref "SW0") (pin "4") (pinfunction "4_4") (pintype "unspecified+no_connect"))
    )
    (net (code "204") (name "unconnected-(SW0-Pad5)") (class "Default")
      (node (ref "SW0") (pin "5") (pinfunction "5_5") (pintype "unspecified+no_connect"))
    )
    (net (code "205") (name "unconnected-(SW1-Pad4)") (class "Default")
      (node (ref "SW1") (pin "4") (pinfunction "4_4") (pintype "unspecified+no_connect"))
    )
    (net (code "206") (name "unconnected-(SW1-Pad5)") (class "Default")
      (node (ref "SW1") (pin "5") (pinfunction "5_5") (pintype "unspecified+no_connect"))
    )
    (net (code "207") (name "unconnected-(SW2-Pad4)") (class "Default")
      (node (ref "SW2") (pin "4") (pinfunction "4_4") (pintype "unspecified+no_connect"))
    )
    (net (code "208") (name "unconnected-(SW2-Pad5)") (class "Default")
      (node (ref "SW2") (pin "5") (pinfunction "5_5") (pintype "unspecified+no_connect"))
    )
    (net (code "209") (name "unconnected-(SW3-Pad4)") (class "Default")
      (node (ref "SW3") (pin "4") (pinfunction "4_4") (pintype "unspecified+no_connect"))
    )
    (net (code "210") (name "unconnected-(SW3-Pad5)") (class "Default")
      (node (ref "SW3") (pin "5") (pinfunction "5_5") (pintype "unspecified+no_connect"))
    )
    (net (code "211") (name "unconnected-(SW4-Pad4)") (class "Default")
      (node (ref "SW4") (pin "4") (pinfunction "4_4") (pintype "unspecified+no_connect"))
    )
    (net (code "212") (name "unconnected-(SW4-Pad5)") (class "Default")
      (node (ref "SW4") (pin "5") (pinfunction "5_5") (pintype "unspecified+no_connect"))
    )
    (net (code "213") (name "unconnected-(SW5-Pad4)") (class "Default")
      (node (ref "SW5") (pin "4") (pinfunction "4_4") (pintype "unspecified+no_connect"))
    )
    (net (code "214") (name "unconnected-(SW5-Pad5)") (class "Default")
      (node (ref "SW5") (pin "5") (pinfunction "5_5") (pintype "unspecified+no_connect"))
    )
    (net (code "215") (name "unconnected-(SW6-Pad4)") (class "Default")
      (node (ref "SW6") (pin "4") (pinfunction "4_4") (pintype "unspecified+no_connect"))
    )
    (net (code "216") (name "unconnected-(SW6-Pad5)") (class "Default")
      (node (ref "SW6") (pin "5") (pinfunction "5_5") (pintype "unspecified+no_connect"))
    )
    (net (code "217") (name "unconnected-(SW7-Pad4)") (class "Default")
      (node (ref "SW7") (pin "4") (pinfunction "4_4") (pintype "unspecified+no_connect"))
    )
    (net (code "218") (name "unconnected-(SW7-Pad5)") (class "Default")
      (node (ref "SW7") (pin "5") (pinfunction "5_5") (pintype "unspecified+no_connect"))
    )
    (net (code "219") (name "unconnected-(SW8-Pad4)") (class "Default")
      (node (ref "SW8") (pin "4") (pinfunction "4_4") (pintype "unspecified+no_connect"))
    )
    (net (code "220") (name "unconnected-(SW8-Pad5)") (class "Default")
      (node (ref "SW8") (pin "5") (pinfunction "5_5") (pintype "unspecified+no_connect"))
    )
    (net (code "221") (name "unconnected-(SW9-Pad4)") (class "Default")
      (node (ref "SW9") (pin "4") (pinfunction "4_4") (pintype "unspecified+no_connect"))
    )
    (net (code "222") (name "unconnected-(SW9-Pad5)") (class "Default")
      (node (ref "SW9") (pin "5") (pinfunction "5_5") (pintype "unspecified+no_connect"))
    )
    (net (code "223") (name "unconnected-(SW17-Pad1)") (class "Default")
      (node (ref "SW17") (pin "1") (pinfunction "1_1") (pintype "unspecified+no_connect"))
    )
    (net (code "224") (name "unconnected-(SW17-Pad4)") (class "Default")
      (node (ref "SW17") (pin "4") (pinfunction "4_4") (pintype "unspecified+no_connect"))
    )
    (net (code "225") (name "unconnected-(SW17-Pad5)") (class "Default")
      (node (ref "SW17") (pin "5") (pinfunction "5_5") (pintype "unspecified+no_connect"))
    )
    (net (code "226") (name "unconnected-(SW17-Pad6)") (class "Default")
      (node (ref "SW17") (pin "6") (pinfunction "6_6") (pintype "unspecified+no_connect"))
    )
    (net (code "227") (name "unconnected-(SW17-Pad7)") (class "Default")
      (node (ref "SW17") (pin "7") (pinfunction "7_7") (pintype "unspecified+no_connect"))
    )
    (net (code "228") (name "unconnected-(U1-IO-Pad1)") (class "Default")
      (node (ref "U1") (pin "1") (pinfunction "IO_1") (pintype "unspecified"))
    )
    (net (code "229") (name "unconnected-(U1-IO-Pad39)") (class "Default")
      (node (ref "U1") (pin "39") (pinfunction "IO_39") (pintype "unspecified"))
    )
    (net (code "230") (name "unconnected-(U1-IO{slash}CLK0-Pad18)") (class "Default")
      (node (ref "U1") (pin "18") (pinfunction "IO/CLK0_18") (pintype "unspecified"))
    )
    (net (code "231") (name "unconnected-(U1-IO{slash}DIFFIO_B1n-Pad38)") (class "Default")
      (node (ref "U1") (pin "38") (pinfunction "IO/DIFFIO_B1n_38") (pintype "unspecified"))
    )
    (net (code "232") (name "unconnected-(U1-IO{slash}DIFFIO_B1p-Pad37)") (class "Default")
      (node (ref "U1") (pin "37") (pinfunction "IO/DIFFIO_B1p_37") (pintype "unspecified"))
    )
    (net (code "233") (name "unconnected-(U1-IO{slash}DIFFIO_B2p-Pad40)") (class "Default")
      (node (ref "U1") (pin "40") (pinfunction "IO/DIFFIO_B2p_40") (pintype "unspecified"))
    )
    (net (code "234") (name "unconnected-(U1-IO{slash}DIFFIO_L1n-Pad3)") (class "Default")
      (node (ref "U1") (pin "3") (pinfunction "IO/DIFFIO_L1n_3") (pintype "unspecified"))
    )
    (net (code "235") (name "unconnected-(U1-IO{slash}DIFFIO_L1p-Pad2)") (class "Default")
      (node (ref "U1") (pin "2") (pinfunction "IO/DIFFIO_L1p_2") (pintype "unspecified"))
    )
    (net (code "236") (name "unconnected-(U1-IO{slash}DIFFIO_L2n-Pad5)") (class "Default")
      (node (ref "U1") (pin "5") (pinfunction "IO/DIFFIO_L2n_5") (pintype "unspecified"))
    )
    (net (code "237") (name "unconnected-(U1-IO{slash}DIFFIO_L2p-Pad4)") (class "Default")
      (node (ref "U1") (pin "4") (pinfunction "IO/DIFFIO_L2p_4") (pintype "unspecified"))
    )
    (net (code "238") (name "unconnected-(U1-IO{slash}DIFFIO_L7p-Pad21)") (class "Default")
      (node (ref "U1") (pin "21") (pinfunction "IO/DIFFIO_L7p_21") (pintype "unspecified"))
    )
    (net (code "239") (name "unconnected-(U1-IO{slash}DIFFIO_L11n-Pad32)") (class "Default")
      (node (ref "U1") (pin "32") (pinfunction "IO/DIFFIO_L11n_32") (pintype "unspecified"))
    )
    (net (code "240") (name "unconnected-(U2-NC-Pad4)") (class "Default")
      (node (ref "U2") (pin "4") (pinfunction "NC_4") (pintype "unspecified+no_connect"))
    )
    (net (code "241") (name "unconnected-(U3-NC-Pad4)") (class "Default")
      (node (ref "U3") (pin "4") (pinfunction "NC_4") (pintype "unspecified+no_connect"))
    )
    (net (code "242") (name "unconnected-(U6-EH-Pad7)") (class "Default")
      (node (ref "U6") (pin "7") (pinfunction "EH_7") (pintype "unspecified+no_connect"))
    )
  )
)
